# MotherForSmoothie_0.net
KiCad netlist of a schematic drawn in EAGLE
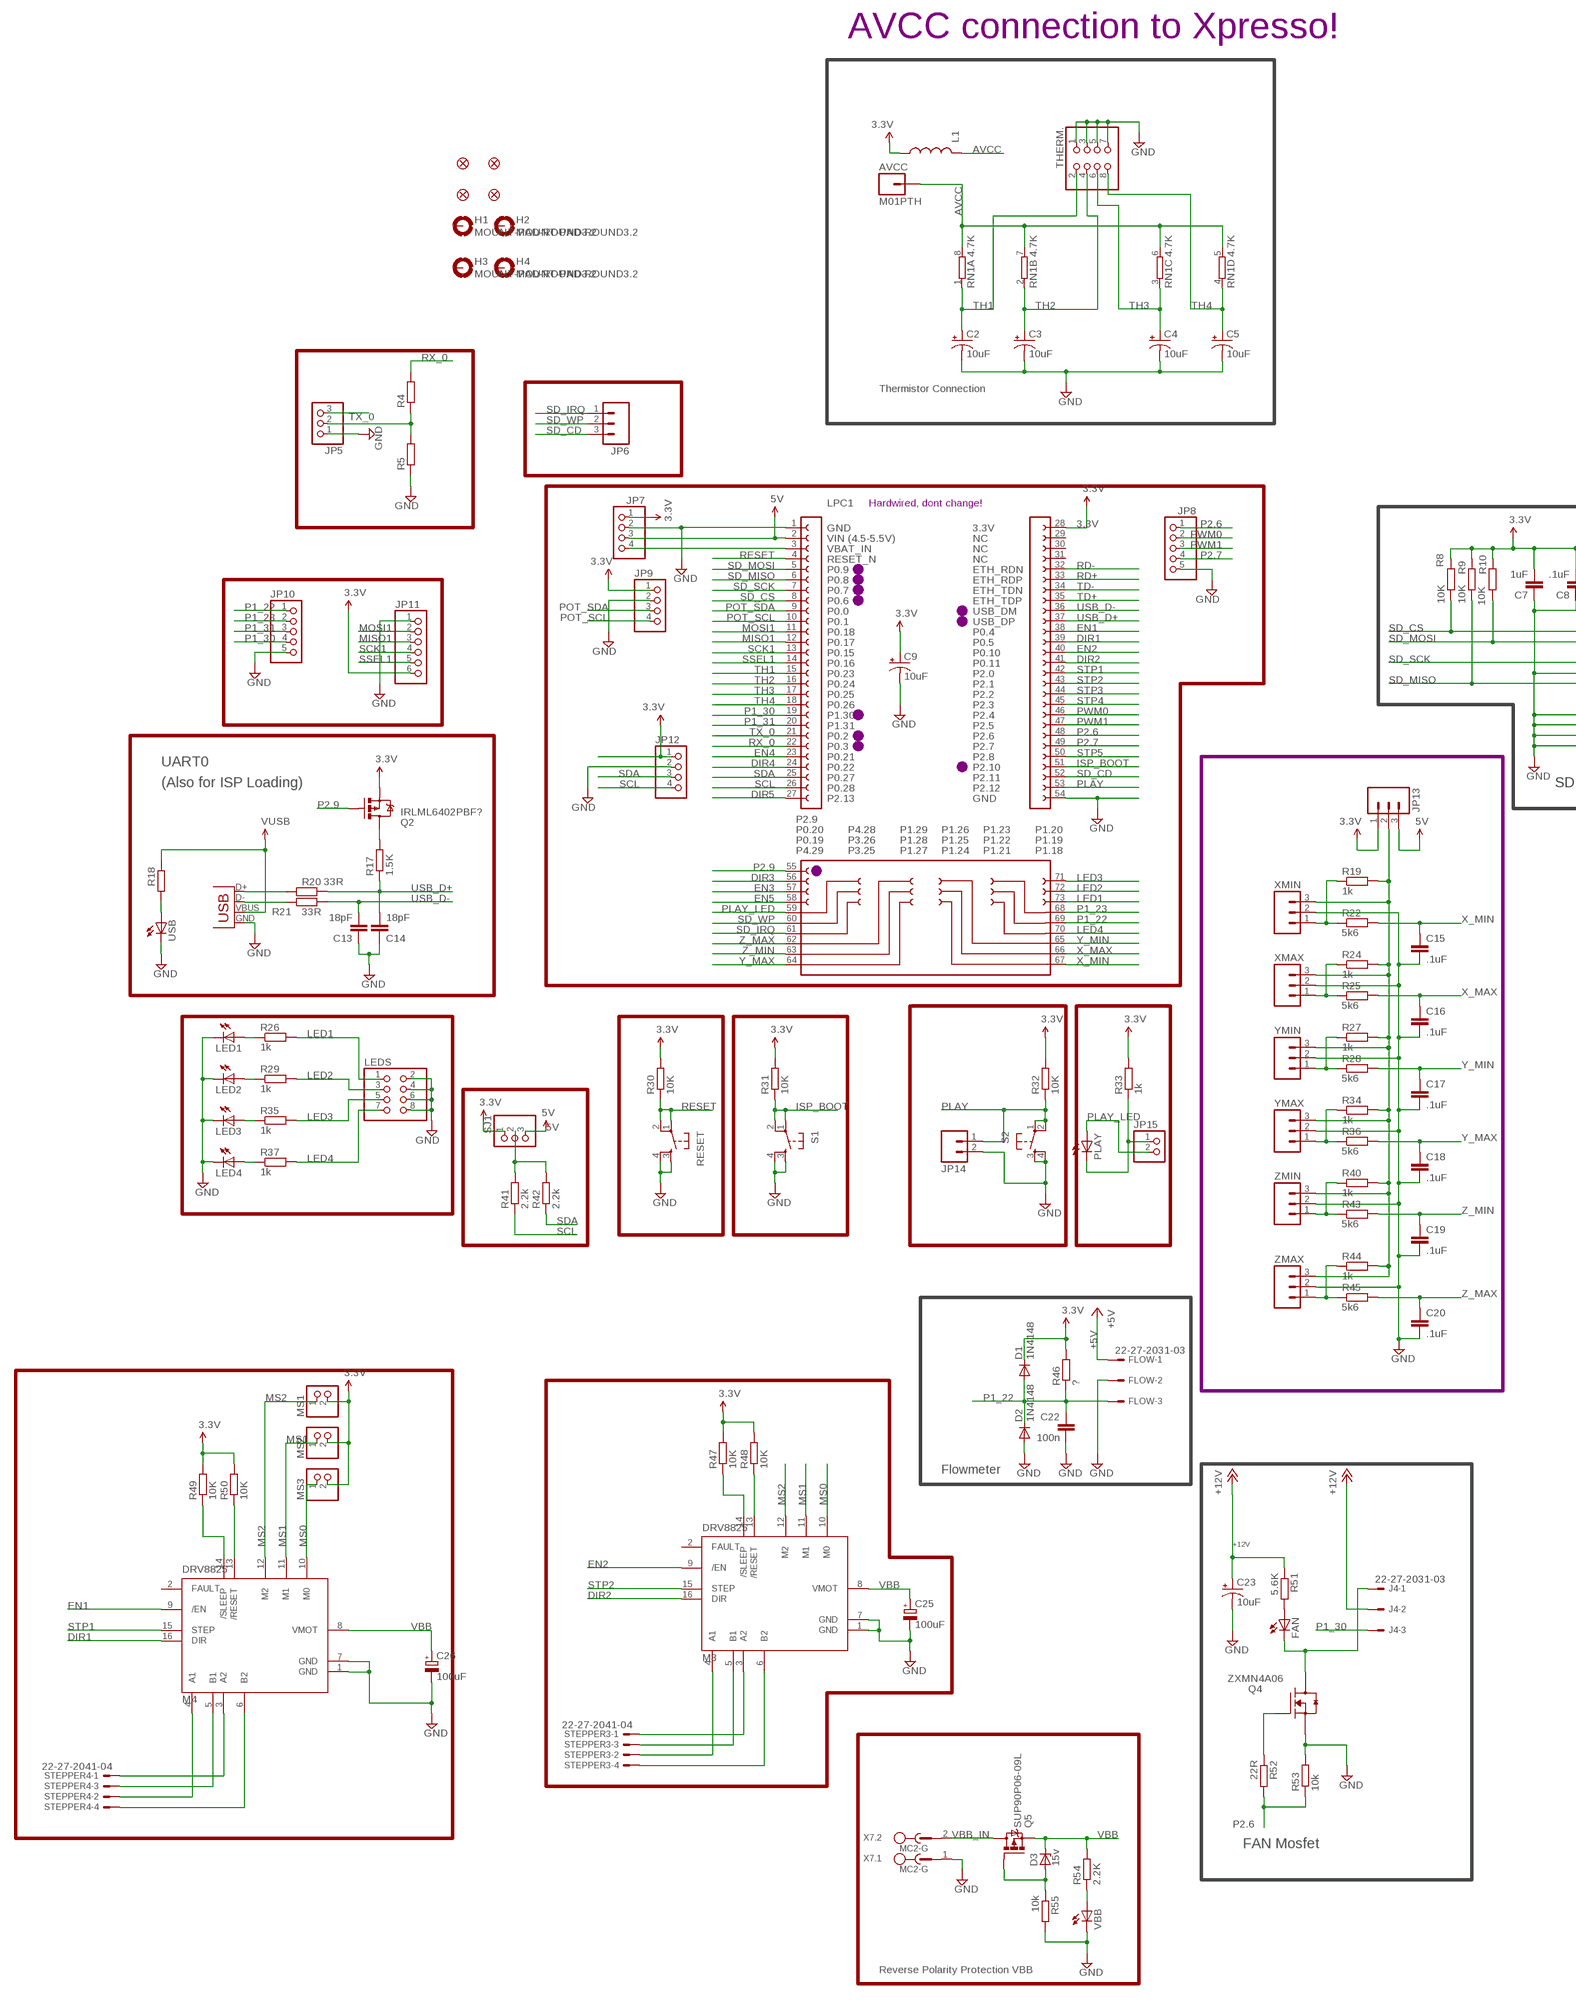
[diagram p0: schematic, sheet 1, part 1 of 2]
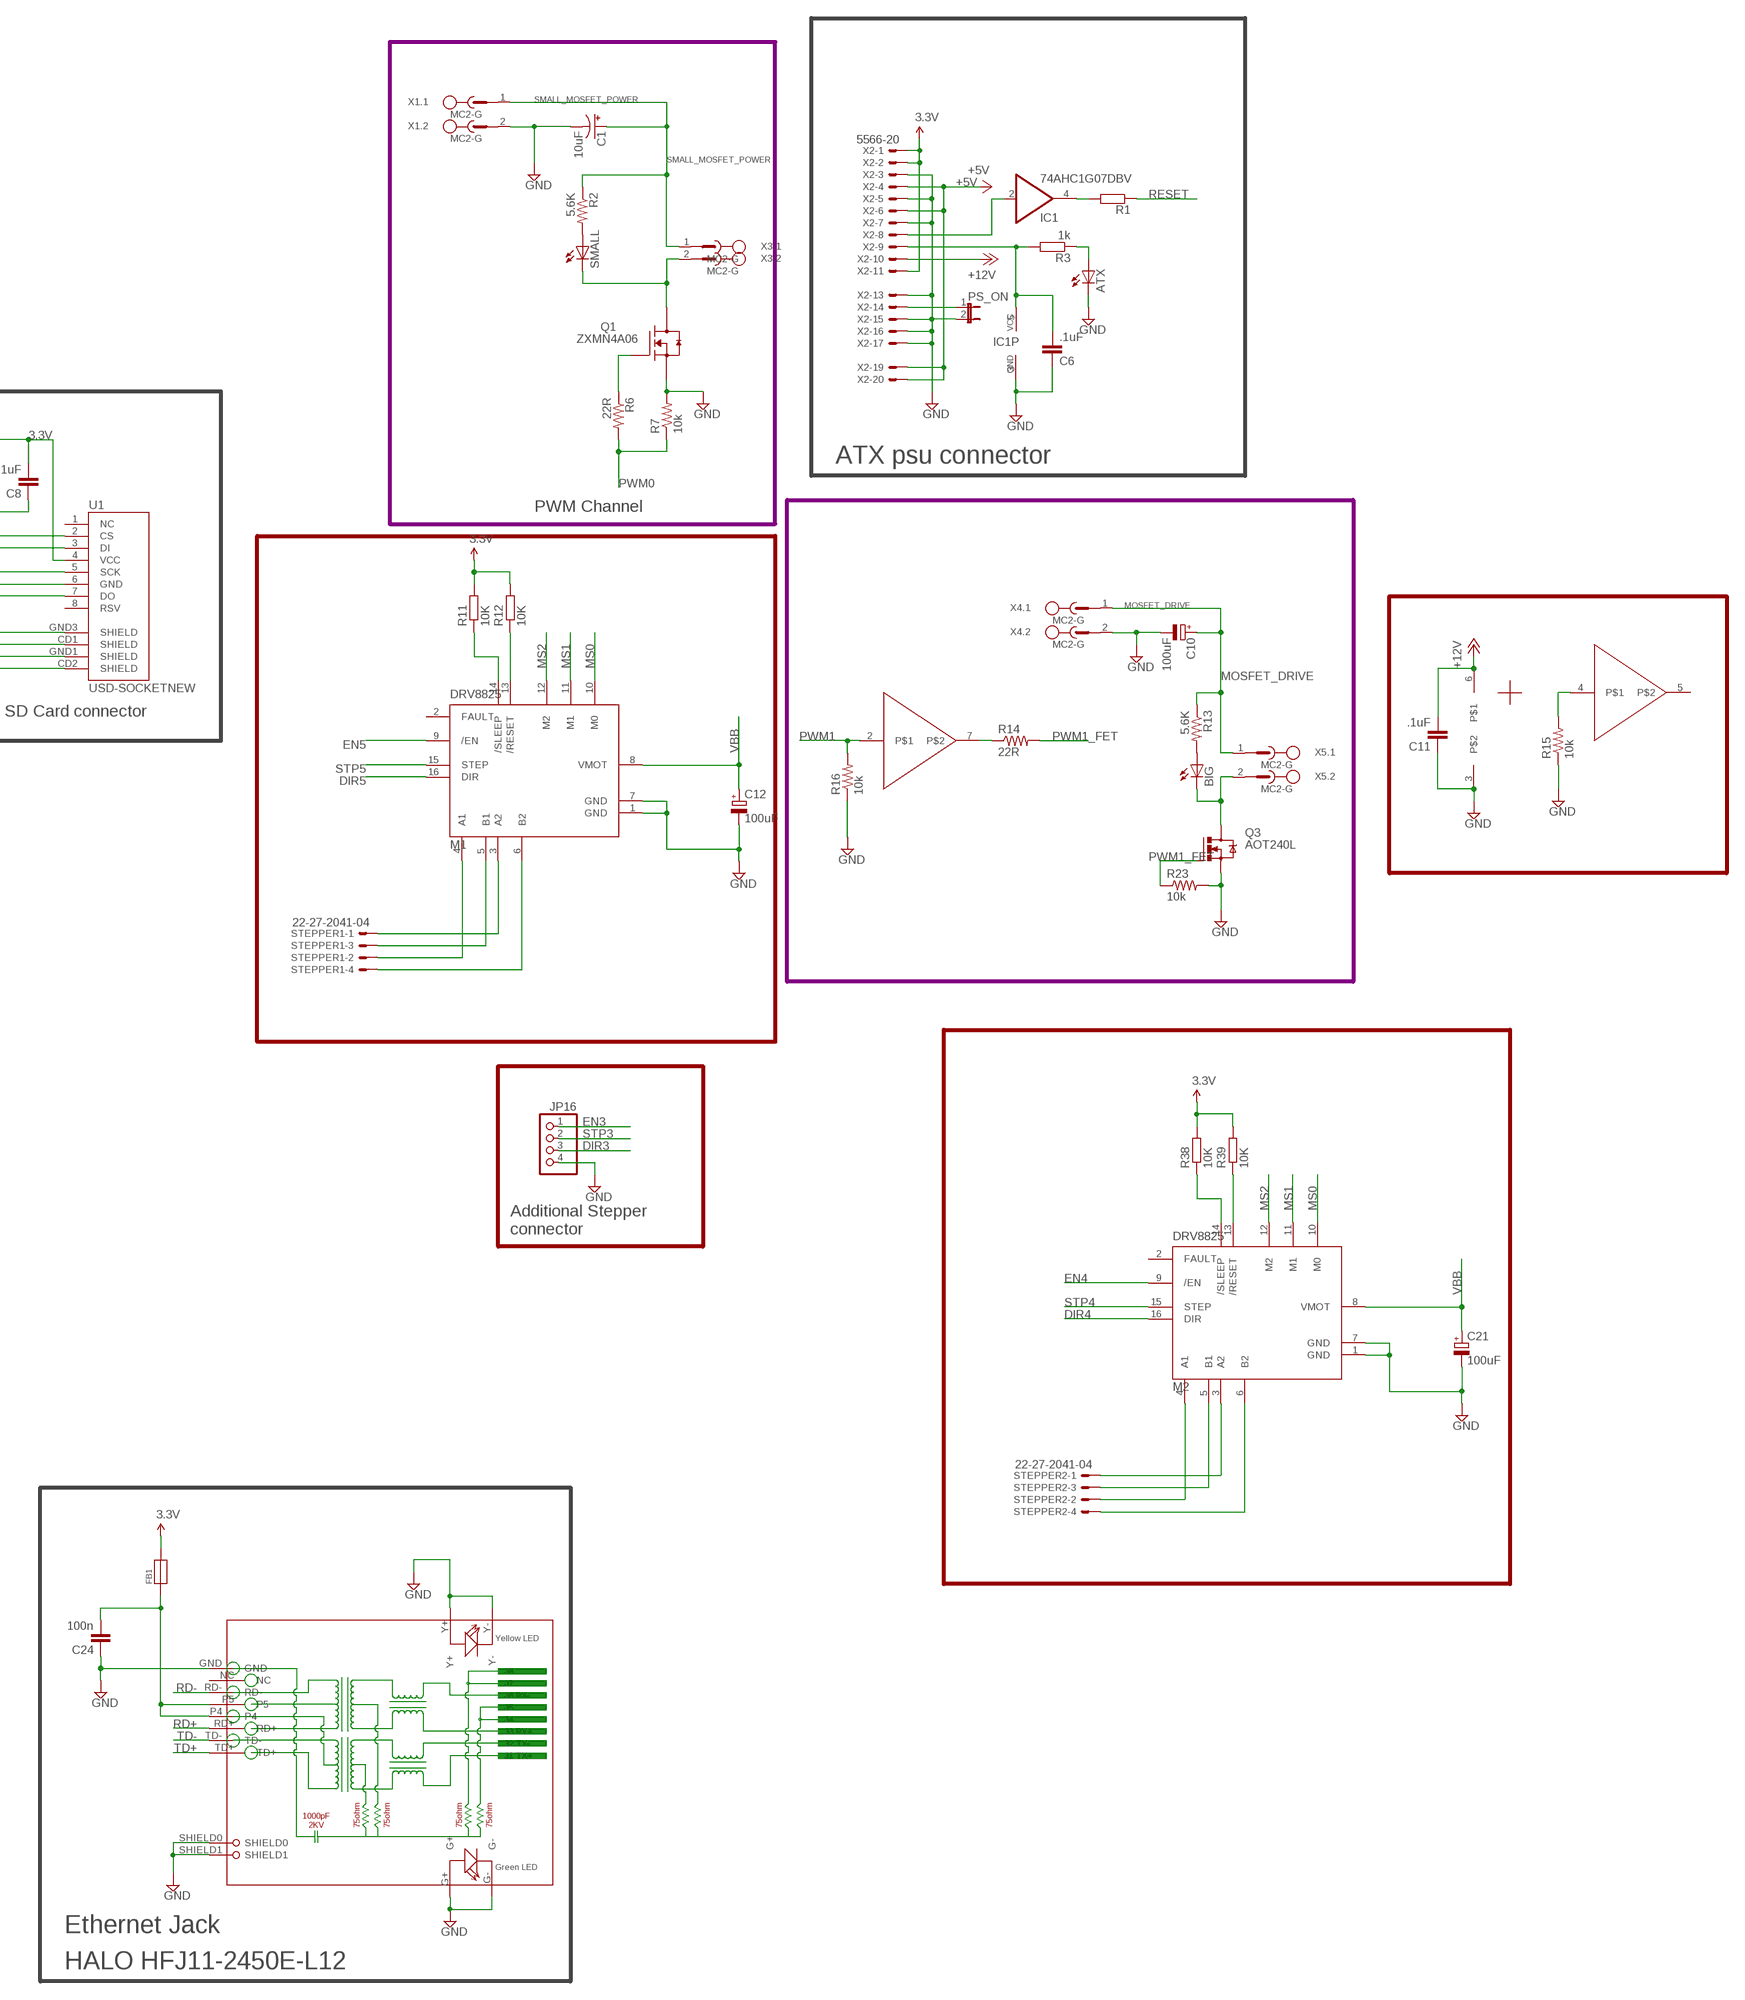
[diagram p1: schematic, sheet 1, part 2 of 2]

(export (version "E")
  (design (tool "Eeschema 10.0.6"))
  (components
    (comp (ref "ATX")
      (value "LEDCHIPLED_0805")
      (footprint "eagle-import:CHIPLED_0805")
      (libsource (lib "eagle-import") (part "LEDCHIPLED_0805"))
    )
    (comp (ref "AVCC")
      (value "M01PTH")
      (footprint "eagle-import:1X01")
      (libsource (lib "eagle-import") (part "M01PTH"))
    )
    (comp (ref "BIG")
      (value "LEDCHIP-LED0805")
      (footprint "eagle-import:CHIP-LED0805")
      (libsource (lib "eagle-import") (part "LEDCHIP-LED0805"))
    )
    (comp (ref "C1")
      (value "10uF")
      (footprint "eagle-import:EIA3216")
      (libsource (lib "eagle-import") (part "CAP_POL1206"))
    )
    (comp (ref "C2")
      (value "10uF")
      (footprint "eagle-import:EIA3216")
      (libsource (lib "eagle-import") (part "CAP_POL1206"))
    )
    (comp (ref "C3")
      (value "10uF")
      (footprint "eagle-import:EIA3216")
      (libsource (lib "eagle-import") (part "CAP_POL1206"))
    )
    (comp (ref "C4")
      (value "10uF")
      (footprint "eagle-import:EIA3216")
      (libsource (lib "eagle-import") (part "CAP_POL1206"))
    )
    (comp (ref "C5")
      (value "10uF")
      (footprint "eagle-import:EIA3216")
      (libsource (lib "eagle-import") (part "CAP_POL1206"))
    )
    (comp (ref "C6")
      (value ".1uF")
      (footprint "eagle-import:C0603")
      (libsource (lib "eagle-import") (part "C-EUC0603"))
    )
    (comp (ref "C7")
      (value "1uF")
      (footprint "eagle-import:C0603")
      (libsource (lib "eagle-import") (part "C-EUC0603"))
    )
    (comp (ref "C8")
      (value ".1uF")
      (footprint "eagle-import:C0603")
      (libsource (lib "eagle-import") (part "C-EUC0603"))
    )
    (comp (ref "C9")
      (value "10uF")
      (footprint "eagle-import:EIA6032")
      (libsource (lib "eagle-import") (part "CAP_POL6032"))
    )
    (comp (ref "C10")
      (value "100uF")
      (footprint "eagle-import:E5-8,5")
      (libsource (lib "eagle-import") (part "CPOL-EUE5-8.5"))
    )
    (comp (ref "C11")
      (value ".1uF")
      (footprint "eagle-import:C0603")
      (libsource (lib "eagle-import") (part "C-EUC0603"))
    )
    (comp (ref "C12")
      (value "100uF")
      (footprint "eagle-import:E5-8,5")
      (libsource (lib "eagle-import") (part "CPOL-EUE5-8.5"))
    )
    (comp (ref "C13")
      (value "18pF")
      (footprint "eagle-import:C0603")
      (libsource (lib "eagle-import") (part "C-EUC0603"))
    )
    (comp (ref "C14")
      (value "18pF")
      (footprint "eagle-import:C0603")
      (libsource (lib "eagle-import") (part "C-EUC0603"))
    )
    (comp (ref "C15")
      (value ".1uF")
      (footprint "eagle-import:C0603")
      (libsource (lib "eagle-import") (part "C-EUC0603"))
    )
    (comp (ref "C16")
      (value ".1uF")
      (footprint "eagle-import:C0603")
      (libsource (lib "eagle-import") (part "C-EUC0603"))
    )
    (comp (ref "C17")
      (value ".1uF")
      (footprint "eagle-import:C0603")
      (libsource (lib "eagle-import") (part "C-EUC0603"))
    )
    (comp (ref "C18")
      (value ".1uF")
      (footprint "eagle-import:C0603")
      (libsource (lib "eagle-import") (part "C-EUC0603"))
    )
    (comp (ref "C19")
      (value ".1uF")
      (footprint "eagle-import:C0603")
      (libsource (lib "eagle-import") (part "C-EUC0603"))
    )
    (comp (ref "C20")
      (value ".1uF")
      (footprint "eagle-import:C0603")
      (libsource (lib "eagle-import") (part "C-EUC0603"))
    )
    (comp (ref "C21")
      (value "100uF")
      (footprint "eagle-import:E5-8,5")
      (libsource (lib "eagle-import") (part "CPOL-EUE5-8.5"))
    )
    (comp (ref "C22")
      (value "100n")
      (footprint "eagle-import:C0603")
      (libsource (lib "eagle-import") (part "C-EUC0603"))
    )
    (comp (ref "C23")
      (value "10uF")
      (footprint "eagle-import:EIA3216")
      (libsource (lib "eagle-import") (part "CAP_POL1206"))
    )
    (comp (ref "C24")
      (value "100n")
      (footprint "eagle-import:C0603")
      (libsource (lib "eagle-import") (part "C-EUC0603"))
    )
    (comp (ref "C25")
      (value "100uF")
      (footprint "eagle-import:E5-8,5")
      (libsource (lib "eagle-import") (part "CPOL-EUE5-8.5"))
    )
    (comp (ref "C26")
      (value "100uF")
      (footprint "eagle-import:E5-8,5")
      (libsource (lib "eagle-import") (part "CPOL-EUE5-8.5"))
    )
    (comp (ref "D1")
      (value "1N4148")
      (footprint "eagle-import:MINIMELF")
      (libsource (lib "eagle-import") (part "DIODE-MINIMELF"))
    )
    (comp (ref "D2")
      (value "1N4148")
      (footprint "eagle-import:MINIMELF")
      (libsource (lib "eagle-import") (part "DIODE-MINIMELF"))
    )
    (comp (ref "D3")
      (value "15v")
      (footprint "eagle-import:SMB")
      (libsource (lib "eagle-import") (part "ZENER-DIODESMB"))
    )
    (comp (ref "FAN")
      (value "LEDCHIPLED_0805")
      (footprint "eagle-import:CHIPLED_0805")
      (libsource (lib "eagle-import") (part "LEDCHIPLED_0805"))
    )
    (comp (ref "FB1")
      (value "FERRITE")
      (footprint "eagle-import:0603")
      (libsource (lib "eagle-import") (part "FERRITE"))
    )
    (comp (ref "FLOW")
      (value "22-27-2031-03")
      (footprint "eagle-import:6410-03")
      (libsource (lib "eagle-import") (part "22-?-0327-2031"))
    )
    (comp (ref "H1")
      (value "MOUNT-PAD-ROUND3.2")
      (footprint "eagle-import:3,2-PAD")
      (libsource (lib "eagle-import") (part "MOUNT-PAD-ROUND3.2"))
    )
    (comp (ref "H2")
      (value "MOUNT-PAD-ROUND3.2")
      (footprint "eagle-import:3,2-PAD")
      (libsource (lib "eagle-import") (part "MOUNT-PAD-ROUND3.2"))
    )
    (comp (ref "H3")
      (value "MOUNT-PAD-ROUND3.2")
      (footprint "eagle-import:3,2-PAD")
      (libsource (lib "eagle-import") (part "MOUNT-PAD-ROUND3.2"))
    )
    (comp (ref "H4")
      (value "MOUNT-PAD-ROUND3.2")
      (footprint "eagle-import:3,2-PAD")
      (libsource (lib "eagle-import") (part "MOUNT-PAD-ROUND3.2"))
    )
    (comp (ref "IC1")
      (value "74AHC1G07DBV")
      (footprint "eagle-import:SOT23-5")
      (libsource (lib "eagle-import") (part "741G07DBVAHC"))
    )
    (comp (ref "IC2")
      (value "TC4427")
      (footprint "eagle-import:SOIC8")
      (libsource (lib "eagle-import") (part "TC4427"))
    )
    (comp (ref "J4")
      (value "22-27-2031-03")
      (footprint "eagle-import:6410-03")
      (libsource (lib "eagle-import") (part "22-?-0327-2031"))
    )
    (comp (ref "JP1")
      (value "FIDUCIAL1X2")
      (footprint "eagle-import:FIDUCIAL-1X2")
      (libsource (lib "eagle-import") (part "FIDUCIAL1X2"))
    )
    (comp (ref "JP2")
      (value "FIDUCIAL1X2")
      (footprint "eagle-import:FIDUCIAL-1X2")
      (libsource (lib "eagle-import") (part "FIDUCIAL1X2"))
    )
    (comp (ref "JP3")
      (value "FIDUCIAL1X2")
      (footprint "eagle-import:FIDUCIAL-1X2")
      (libsource (lib "eagle-import") (part "FIDUCIAL1X2"))
    )
    (comp (ref "JP4")
      (value "FIDUCIAL1X2")
      (footprint "eagle-import:FIDUCIAL-1X2")
      (libsource (lib "eagle-import") (part "FIDUCIAL1X2"))
    )
    (comp (ref "JP5")
      (value "PINHD-1X3_2.54-SMD")
      (footprint "eagle-import:1X03SMD")
      (libsource (lib "eagle-import") (part "PINHD-1X3_2.54-SMD"))
    )
    (comp (ref "JP6")
      (value "M031X03_NO_SILK")
      (footprint "eagle-import:1X03_NO_SILK")
      (libsource (lib "eagle-import") (part "M031X03_NO_SILK"))
    )
    (comp (ref "JP7")
      (value "PINHD-1X4_2.54-SMD")
      (footprint "eagle-import:1X04SMD")
      (libsource (lib "eagle-import") (part "PINHD-1X4_2.54-SMD"))
    )
    (comp (ref "JP8")
      (value "PINHD-1X5_2.54-SMD")
      (footprint "eagle-import:1X05SMD")
      (libsource (lib "eagle-import") (part "PINHD-1X5_2.54-SMD"))
    )
    (comp (ref "JP9")
      (value "PINHD-1X4_2.54-SMD")
      (footprint "eagle-import:1X04SMD")
      (libsource (lib "eagle-import") (part "PINHD-1X4_2.54-SMD"))
    )
    (comp (ref "JP10")
      (value "PINHD-1X5_2.54-SMD")
      (footprint "eagle-import:1X05SMD")
      (libsource (lib "eagle-import") (part "PINHD-1X5_2.54-SMD"))
    )
    (comp (ref "JP11")
      (value "PINHD-1X6_2.54-SMD")
      (footprint "eagle-import:1X06SMD")
      (libsource (lib "eagle-import") (part "PINHD-1X6_2.54-SMD"))
    )
    (comp (ref "JP12")
      (value "PINHD-1X4_2.54-SMD")
      (footprint "eagle-import:1X04SMD")
      (libsource (lib "eagle-import") (part "PINHD-1X4_2.54-SMD"))
    )
    (comp (ref "JP13")
      (value "M031X03_NO_SILK")
      (footprint "eagle-import:1X03_NO_SILK")
      (libsource (lib "eagle-import") (part "M031X03_NO_SILK"))
    )
    (comp (ref "JP14")
      (value "M02PTH")
      (footprint "eagle-import:1X02")
      (libsource (lib "eagle-import") (part "M02PTH"))
    )
    (comp (ref "JP15")
      (value "PINHD-1X2_2.54-SMD")
      (footprint "eagle-import:1X02SMD")
      (libsource (lib "eagle-import") (part "PINHD-1X2_2.54-SMD"))
    )
    (comp (ref "JP16")
      (value "PINHD-1X4_2.54-SMD")
      (footprint "eagle-import:1X04SMD")
      (libsource (lib "eagle-import") (part "PINHD-1X4_2.54-SMD"))
    )
    (comp (ref "L1")
      (value "INDUCTOR0603")
      (footprint "eagle-import:0603")
      (libsource (lib "eagle-import") (part "INDUCTOR0603"))
    )
    (comp (ref "LED1")
      (value "LEDCHIP-LED0805")
      (footprint "eagle-import:CHIP-LED0805")
      (libsource (lib "eagle-import") (part "LEDCHIP-LED0805"))
    )
    (comp (ref "LED2")
      (value "LEDCHIP-LED0805")
      (footprint "eagle-import:CHIP-LED0805")
      (libsource (lib "eagle-import") (part "LEDCHIP-LED0805"))
    )
    (comp (ref "LED3")
      (value "LEDCHIP-LED0805")
      (footprint "eagle-import:CHIP-LED0805")
      (libsource (lib "eagle-import") (part "LEDCHIP-LED0805"))
    )
    (comp (ref "LED4")
      (value "LEDCHIP-LED0805")
      (footprint "eagle-import:CHIP-LED0805")
      (libsource (lib "eagle-import") (part "LEDCHIP-LED0805"))
    )
    (comp (ref "LEDS")
      (value "PINHD-2X4_2.54-SMD")
      (footprint "eagle-import:2X04SMD")
      (libsource (lib "eagle-import") (part "PINHD-2X4_2.54-SMD"))
    )
    (comp (ref "LPC1")
      (value "LPCXPRESSO_LPC1769SMD_PART")
      (footprint "eagle-import:LPCXPRESSO_LPC1769_SMD")
      (libsource (lib "eagle-import") (part "LPCXPRESSO_LPC1769SMD_PART"))
    )
    (comp (ref "M1")
      (value "DRV8825")
      (footprint "eagle-import:DRV8825")
      (libsource (lib "eagle-import") (part "DRV8825"))
    )
    (comp (ref "M2")
      (value "DRV8825")
      (footprint "eagle-import:DRV8825")
      (libsource (lib "eagle-import") (part "DRV8825"))
    )
    (comp (ref "M3")
      (value "DRV8825")
      (footprint "eagle-import:DRV8825")
      (libsource (lib "eagle-import") (part "DRV8825"))
    )
    (comp (ref "M4")
      (value "DRV8825")
      (footprint "eagle-import:DRV8825")
      (libsource (lib "eagle-import") (part "DRV8825"))
    )
    (comp (ref "MS1")
      (value "PINHD-1X2_2.54-SMD")
      (footprint "eagle-import:1X02SMD")
      (libsource (lib "eagle-import") (part "PINHD-1X2_2.54-SMD"))
    )
    (comp (ref "MS2")
      (value "PINHD-1X2_2.54-SMD")
      (footprint "eagle-import:1X02SMD")
      (libsource (lib "eagle-import") (part "PINHD-1X2_2.54-SMD"))
    )
    (comp (ref "MS3")
      (value "PINHD-1X2_2.54-SMD")
      (footprint "eagle-import:1X02SMD")
      (libsource (lib "eagle-import") (part "PINHD-1X2_2.54-SMD"))
    )
    (comp (ref "PLAY")
      (value "LEDCHIPLED_0805")
      (footprint "eagle-import:CHIPLED_0805")
      (libsource (lib "eagle-import") (part "LEDCHIPLED_0805"))
    )
    (comp (ref "PS_ON")
      (value "JP1E")
      (footprint "eagle-import:JP1")
      (libsource (lib "eagle-import") (part "JP1E"))
    )
    (comp (ref "Q1")
      (value "ZXMN4A06")
      (footprint "eagle-import:SOT230P700X160-4N")
      (libsource (lib "eagle-import") (part "MOSFET-NCH_SOT-223"))
    )
    (comp (ref "Q2")
      (value "IRLML6402PBF?")
      (footprint "eagle-import:SOT23-3")
      (libsource (lib "eagle-import") (part "MOSFET-PCHANNELSMD"))
    )
    (comp (ref "Q3")
      (value "AOT240L")
      (footprint "eagle-import:TO220BV")
      (libsource (lib "eagle-import") (part "IRF540"))
    )
    (comp (ref "Q4")
      (value "ZXMN4A06")
      (footprint "eagle-import:SOT230P700X160-4N")
      (libsource (lib "eagle-import") (part "MOSFET-NCH_SOT-223"))
    )
    (comp (ref "Q5")
      (value "SUP90P06-09L")
      (footprint "eagle-import:TO220BV")
      (libsource (lib "eagle-import") (part "IRF9530"))
    )
    (comp (ref "R1")
      (value "R-EU_R0603")
      (footprint "eagle-import:R0603")
      (libsource (lib "eagle-import") (part "R-EU_R0603"))
    )
    (comp (ref "R2")
      (value "5.6K")
      (footprint "eagle-import:R0603")
      (libsource (lib "eagle-import") (part "R-US_R0603"))
    )
    (comp (ref "R3")
      (value "1k")
      (footprint "eagle-import:R0603")
      (libsource (lib "eagle-import") (part "R-EU_R0603"))
    )
    (comp (ref "R4")
      (value "R-EU_R0603")
      (footprint "eagle-import:R0603")
      (libsource (lib "eagle-import") (part "R-EU_R0603"))
    )
    (comp (ref "R5")
      (value "R-EU_R0603")
      (footprint "eagle-import:R0603")
      (libsource (lib "eagle-import") (part "R-EU_R0603"))
    )
    (comp (ref "R6")
      (value "22R")
      (footprint "eagle-import:R0603")
      (libsource (lib "eagle-import") (part "R-US_R0603"))
    )
    (comp (ref "R7")
      (value "10k")
      (footprint "eagle-import:R0603")
      (libsource (lib "eagle-import") (part "R-US_R0603"))
    )
    (comp (ref "R8")
      (value "10K")
      (footprint "eagle-import:R0603")
      (libsource (lib "eagle-import") (part "R-EU_R0603"))
    )
    (comp (ref "R9")
      (value "10K")
      (footprint "eagle-import:R0603")
      (libsource (lib "eagle-import") (part "R-EU_R0603"))
    )
    (comp (ref "R10")
      (value "10K")
      (footprint "eagle-import:R0603")
      (libsource (lib "eagle-import") (part "R-EU_R0603"))
    )
    (comp (ref "R11")
      (value "10K")
      (footprint "eagle-import:R0603")
      (libsource (lib "eagle-import") (part "R-EU_R0603"))
    )
    (comp (ref "R12")
      (value "10K")
      (footprint "eagle-import:R0603")
      (libsource (lib "eagle-import") (part "R-EU_R0603"))
    )
    (comp (ref "R13")
      (value "5.6K")
      (footprint "eagle-import:R0603")
      (libsource (lib "eagle-import") (part "R-US_R0603"))
    )
    (comp (ref "R14")
      (value "22R")
      (footprint "eagle-import:R0603")
      (libsource (lib "eagle-import") (part "R-US_R0603"))
    )
    (comp (ref "R15")
      (value "10k")
      (footprint "eagle-import:R0603")
      (libsource (lib "eagle-import") (part "R-US_R0603"))
    )
    (comp (ref "R16")
      (value "10k")
      (footprint "eagle-import:R0603")
      (libsource (lib "eagle-import") (part "R-US_R0603"))
    )
    (comp (ref "R17")
      (value "1.5K")
      (footprint "eagle-import:R0603")
      (libsource (lib "eagle-import") (part "R-EU_R0603"))
    )
    (comp (ref "R18")
      (value "R-EU_R0603")
      (footprint "eagle-import:R0603")
      (libsource (lib "eagle-import") (part "R-EU_R0603"))
    )
    (comp (ref "R19")
      (value "1k")
      (footprint "eagle-import:R0603")
      (libsource (lib "eagle-import") (part "R-EU_R0603"))
    )
    (comp (ref "R20")
      (value "33R")
      (footprint "eagle-import:R0603")
      (libsource (lib "eagle-import") (part "R-EU_R0603"))
    )
    (comp (ref "R21")
      (value "33R")
      (footprint "eagle-import:R0603")
      (libsource (lib "eagle-import") (part "R-EU_R0603"))
    )
    (comp (ref "R22")
      (value "5k6")
      (footprint "eagle-import:R0603")
      (libsource (lib "eagle-import") (part "R-EU_R0603"))
    )
    (comp (ref "R23")
      (value "10k")
      (footprint "eagle-import:R0603")
      (libsource (lib "eagle-import") (part "R-US_R0603"))
    )
    (comp (ref "R24")
      (value "1k")
      (footprint "eagle-import:R0603")
      (libsource (lib "eagle-import") (part "R-EU_R0603"))
    )
    (comp (ref "R25")
      (value "5k6")
      (footprint "eagle-import:R0603")
      (libsource (lib "eagle-import") (part "R-EU_R0603"))
    )
    (comp (ref "R26")
      (value "1k")
      (footprint "eagle-import:R0603")
      (libsource (lib "eagle-import") (part "R-EU_R0603"))
    )
    (comp (ref "R27")
      (value "1k")
      (footprint "eagle-import:R0603")
      (libsource (lib "eagle-import") (part "R-EU_R0603"))
    )
    (comp (ref "R28")
      (value "5k6")
      (footprint "eagle-import:R0603")
      (libsource (lib "eagle-import") (part "R-EU_R0603"))
    )
    (comp (ref "R29")
      (value "1k")
      (footprint "eagle-import:R0603")
      (libsource (lib "eagle-import") (part "R-EU_R0603"))
    )
    (comp (ref "R30")
      (value "10K")
      (footprint "eagle-import:R0603")
      (libsource (lib "eagle-import") (part "R-EU_R0603"))
    )
    (comp (ref "R31")
      (value "10K")
      (footprint "eagle-import:R0603")
      (libsource (lib "eagle-import") (part "R-EU_R0603"))
    )
    (comp (ref "R32")
      (value "10K")
      (footprint "eagle-import:R0603")
      (libsource (lib "eagle-import") (part "R-EU_R0603"))
    )
    (comp (ref "R33")
      (value "1k")
      (footprint "eagle-import:R0603")
      (libsource (lib "eagle-import") (part "R-EU_R0603"))
    )
    (comp (ref "R34")
      (value "1k")
      (footprint "eagle-import:R0603")
      (libsource (lib "eagle-import") (part "R-EU_R0603"))
    )
    (comp (ref "R35")
      (value "1k")
      (footprint "eagle-import:R0603")
      (libsource (lib "eagle-import") (part "R-EU_R0603"))
    )
    (comp (ref "R36")
      (value "5k6")
      (footprint "eagle-import:R0603")
      (libsource (lib "eagle-import") (part "R-EU_R0603"))
    )
    (comp (ref "R37")
      (value "1k")
      (footprint "eagle-import:R0603")
      (libsource (lib "eagle-import") (part "R-EU_R0603"))
    )
    (comp (ref "R38")
      (value "10K")
      (footprint "eagle-import:R0603")
      (libsource (lib "eagle-import") (part "R-EU_R0603"))
    )
    (comp (ref "R39")
      (value "10K")
      (footprint "eagle-import:R0603")
      (libsource (lib "eagle-import") (part "R-EU_R0603"))
    )
    (comp (ref "R40")
      (value "1k")
      (footprint "eagle-import:R0603")
      (libsource (lib "eagle-import") (part "R-EU_R0603"))
    )
    (comp (ref "R41")
      (value "2.2k")
      (footprint "eagle-import:R0603")
      (libsource (lib "eagle-import") (part "R-EU_R0603"))
    )
    (comp (ref "R42")
      (value "2.2k")
      (footprint "eagle-import:R0603")
      (libsource (lib "eagle-import") (part "R-EU_R0603"))
    )
    (comp (ref "R43")
      (value "5k6")
      (footprint "eagle-import:R0603")
      (libsource (lib "eagle-import") (part "R-EU_R0603"))
    )
    (comp (ref "R44")
      (value "1k")
      (footprint "eagle-import:R0603")
      (libsource (lib "eagle-import") (part "R-EU_R0603"))
    )
    (comp (ref "R45")
      (value "5k6")
      (footprint "eagle-import:R0603")
      (libsource (lib "eagle-import") (part "R-EU_R0603"))
    )
    (comp (ref "R46")
      (value "?")
      (footprint "eagle-import:R0603")
      (libsource (lib "eagle-import") (part "R-EU_R0603"))
    )
    (comp (ref "R47")
      (value "10K")
      (footprint "eagle-import:R0603")
      (libsource (lib "eagle-import") (part "R-EU_R0603"))
    )
    (comp (ref "R48")
      (value "10K")
      (footprint "eagle-import:R0603")
      (libsource (lib "eagle-import") (part "R-EU_R0603"))
    )
    (comp (ref "R49")
      (value "10K")
      (footprint "eagle-import:R0603")
      (libsource (lib "eagle-import") (part "R-EU_R0603"))
    )
    (comp (ref "R50")
      (value "10K")
      (footprint "eagle-import:R0603")
      (libsource (lib "eagle-import") (part "R-EU_R0603"))
    )
    (comp (ref "R51")
      (value "5.6K")
      (footprint "eagle-import:R0603")
      (libsource (lib "eagle-import") (part "R-EU_R0603"))
    )
    (comp (ref "R52")
      (value "22R")
      (footprint "eagle-import:R0603")
      (libsource (lib "eagle-import") (part "R-EU_R0603"))
    )
    (comp (ref "R53")
      (value "10k")
      (footprint "eagle-import:R0603")
      (libsource (lib "eagle-import") (part "R-EU_R0603"))
    )
    (comp (ref "R54")
      (value "2.2K")
      (footprint "eagle-import:R0603")
      (libsource (lib "eagle-import") (part "R-EU_R0603"))
    )
    (comp (ref "R55")
      (value "10k")
      (footprint "eagle-import:R0603")
      (libsource (lib "eagle-import") (part "R-EU_R0603"))
    )
    (comp (ref "RESET")
      (value "TAC_SWITCHSMD")
      (footprint "eagle-import:TACTILE_SWITCH_SMD")
      (libsource (lib "eagle-import") (part "TAC_SWITCHSMD"))
    )
    (comp (ref "RJ1")
      (value "HR911105A")
      (footprint "eagle-import:HR911105A")
      (libsource (lib "eagle-import") (part "HR911105A"))
    )
    (comp (ref "RN1")
      (value "4.7K")
      (footprint "eagle-import:0603-ARV")
      (libsource (lib "eagle-import") (part "4R-N0603-ARV"))
    )
    (comp (ref "S1")
      (value "TAC_SWITCHSMD")
      (footprint "eagle-import:TACTILE_SWITCH_SMD")
      (libsource (lib "eagle-import") (part "TAC_SWITCHSMD"))
    )
    (comp (ref "S2")
      (value "TAC_SWITCHSMD")
      (footprint "eagle-import:TACTILE_SWITCH_SMD")
      (libsource (lib "eagle-import") (part "TAC_SWITCHSMD"))
    )
    (comp (ref "SJ1")
      (value "PINHD-1X3_2.54-SMD")
      (footprint "eagle-import:1X03SMD")
      (libsource (lib "eagle-import") (part "PINHD-1X3_2.54-SMD"))
    )
    (comp (ref "SMALL")
      (value "LEDCHIP-LED0805")
      (footprint "eagle-import:CHIP-LED0805")
      (libsource (lib "eagle-import") (part "LEDCHIP-LED0805"))
    )
    (comp (ref "STEPPER1")
      (value "22-27-2041-04")
      (footprint "eagle-import:6410-04")
      (libsource (lib "eagle-import") (part "22-?-0427-2041"))
    )
    (comp (ref "STEPPER2")
      (value "22-27-2041-04")
      (footprint "eagle-import:6410-04")
      (libsource (lib "eagle-import") (part "22-?-0427-2041"))
    )
    (comp (ref "STEPPER3")
      (value "22-27-2041-04")
      (footprint "eagle-import:6410-04")
      (libsource (lib "eagle-import") (part "22-?-0427-2041"))
    )
    (comp (ref "STEPPER4")
      (value "22-27-2041-04")
      (footprint "eagle-import:6410-04")
      (libsource (lib "eagle-import") (part "22-?-0427-2041"))
    )
    (comp (ref "THERM.")
      (value "PINHD-2X4MICROMATCH-SMD")
      (footprint "eagle-import:SMDTOP8")
      (libsource (lib "eagle-import") (part "PINHD-2X4MICROMATCH-SMD"))
    )
    (comp (ref "U1")
      (value "USD-SOCKETNEW")
      (footprint "eagle-import:MICRO-SD-SOCKET-PP")
      (libsource (lib "eagle-import") (part "USD-SOCKETNEW"))
    )
    (comp (ref "USB")
      (value "LEDCHIPLED_0805")
      (footprint "eagle-import:CHIPLED_0805")
      (libsource (lib "eagle-import") (part "LEDCHIPLED_0805"))
    )
    (comp (ref "VBB")
      (value "LEDCHIPLED_0805")
      (footprint "eagle-import:CHIPLED_0805")
      (libsource (lib "eagle-import") (part "LEDCHIPLED_0805"))
    )
    (comp (ref "X1")
      (value "MC2-G")
      (footprint "eagle-import:MC2-G")
      (libsource (lib "eagle-import") (part "MC2-G"))
    )
    (comp (ref "X2")
      (value "5566-20")
      (footprint "eagle-import:5566-20")
      (libsource (lib "eagle-import") (part "5566-20"))
    )
    (comp (ref "X3")
      (value "MC2-G")
      (footprint "eagle-import:MC2-G")
      (libsource (lib "eagle-import") (part "MC2-G"))
    )
    (comp (ref "X4")
      (value "MC2-G")
      (footprint "eagle-import:MC2-G")
      (libsource (lib "eagle-import") (part "MC2-G"))
    )
    (comp (ref "X5")
      (value "MC2-G")
      (footprint "eagle-import:MC2-G")
      (libsource (lib "eagle-import") (part "MC2-G"))
    )
    (comp (ref "X6")
      (value "USB-MICROB")
      (footprint "eagle-import:USB-MICROB")
      (libsource (lib "eagle-import") (part "USB-MICROB"))
    )
    (comp (ref "X7")
      (value "MC2-G")
      (footprint "eagle-import:MC2-G")
      (libsource (lib "eagle-import") (part "MC2-G"))
    )
    (comp (ref "XMAX")
      (value "M031X03_NO_SILK")
      (footprint "eagle-import:1X03_NO_SILK")
      (libsource (lib "eagle-import") (part "M031X03_NO_SILK"))
    )
    (comp (ref "XMIN")
      (value "M031X03_NO_SILK")
      (footprint "eagle-import:1X03_NO_SILK")
      (libsource (lib "eagle-import") (part "M031X03_NO_SILK"))
    )
    (comp (ref "YMAX")
      (value "M031X03_NO_SILK")
      (footprint "eagle-import:1X03_NO_SILK")
      (libsource (lib "eagle-import") (part "M031X03_NO_SILK"))
    )
    (comp (ref "YMIN")
      (value "M031X03_NO_SILK")
      (footprint "eagle-import:1X03_NO_SILK")
      (libsource (lib "eagle-import") (part "M031X03_NO_SILK"))
    )
    (comp (ref "ZMAX")
      (value "M031X03_NO_SILK")
      (footprint "eagle-import:1X03_NO_SILK")
      (libsource (lib "eagle-import") (part "M031X03_NO_SILK"))
    )
    (comp (ref "ZMIN")
      (value "M031X03_NO_SILK")
      (footprint "eagle-import:1X03_NO_SILK")
      (libsource (lib "eagle-import") (part "M031X03_NO_SILK"))
    )
  )
  (nets
    (net (code "1") (name "+5V") (class "Default")
      (node (ref "FLOW") (pin "1") (pinfunction "S_1") (pintype "passive"))
      (node (ref "X2") (pin "19") (pinfunction "S_19") (pintype "passive"))
      (node (ref "X2") (pin "20") (pinfunction "S_20") (pintype "passive"))
      (node (ref "X2") (pin "4") (pinfunction "S_4") (pintype "passive"))
      (node (ref "X2") (pin "6") (pinfunction "S_6") (pintype "passive"))
    )
    (net (code "2") (name "+12V") (class "Default")
      (node (ref "C11") (pin "2") (pinfunction "2_2") (pintype "passive"))
      (node (ref "C23") (pin "A") (pinfunction "+_A") (pintype "passive"))
      (node (ref "IC2") (pin "6") (pinfunction "P$1_6") (pintype "bidirectional"))
      (node (ref "J4") (pin "2") (pinfunction "S_2") (pintype "passive"))
      (node (ref "R51") (pin "1") (pinfunction "1_1") (pintype "passive"))
      (node (ref "X2") (pin "10") (pinfunction "S_10") (pintype "passive"))
    )
    (net (code "3") (name "/AVCC") (class "Default")
      (node (ref "AVCC") (pin "1") (pinfunction "1_1") (pintype "passive"))
      (node (ref "L1") (pin "1") (pinfunction "1_1") (pintype "passive"))
      (node (ref "RN1") (pin "5") (pinfunction "2_5") (pintype "passive"))
      (node (ref "RN1") (pin "6") (pinfunction "2_6") (pintype "passive"))
      (node (ref "RN1") (pin "7") (pinfunction "2_7") (pintype "passive"))
      (node (ref "RN1") (pin "8") (pinfunction "2_8") (pintype "passive"))
    )
    (net (code "4") (name "/DIR1") (class "Default")
      (node (ref "LPC1") (pin "39") (pinfunction "39_39") (pintype "passive"))
      (node (ref "M4") (pin "16") (pinfunction "DIR_16") (pintype "input"))
    )
    (net (code "5") (name "/DIR2") (class "Default")
      (node (ref "LPC1") (pin "41") (pinfunction "41_41") (pintype "passive"))
      (node (ref "M3") (pin "16") (pinfunction "DIR_16") (pintype "input"))
    )
    (net (code "6") (name "/DIR3") (class "Default")
      (node (ref "JP16") (pin "3") (pinfunction "3_3") (pintype "passive"))
      (node (ref "LPC1") (pin "56") (pinfunction "56_56") (pintype "passive"))
    )
    (net (code "7") (name "/DIR4") (class "Default")
      (node (ref "LPC1") (pin "24") (pinfunction "24_24") (pintype "passive"))
      (node (ref "M2") (pin "16") (pinfunction "DIR_16") (pintype "input"))
    )
    (net (code "8") (name "/DIR5") (class "Default")
      (node (ref "LPC1") (pin "27") (pinfunction "27_27") (pintype "passive"))
      (node (ref "M1") (pin "16") (pinfunction "DIR_16") (pintype "input"))
    )
    (net (code "9") (name "/EN1") (class "Default")
      (node (ref "LPC1") (pin "38") (pinfunction "38_38") (pintype "passive"))
      (node (ref "M4") (pin "9") (pinfunction "/EN_9") (pintype "input"))
    )
    (net (code "10") (name "/EN2") (class "Default")
      (node (ref "LPC1") (pin "40") (pinfunction "40_40") (pintype "passive"))
      (node (ref "M3") (pin "9") (pinfunction "/EN_9") (pintype "input"))
    )
    (net (code "11") (name "/EN3") (class "Default")
      (node (ref "JP16") (pin "1") (pinfunction "1_1") (pintype "passive"))
      (node (ref "LPC1") (pin "57") (pinfunction "57_57") (pintype "passive"))
    )
    (net (code "12") (name "/EN4") (class "Default")
      (node (ref "LPC1") (pin "23") (pinfunction "23_23") (pintype "passive"))
      (node (ref "M2") (pin "9") (pinfunction "/EN_9") (pintype "input"))
    )
    (net (code "13") (name "/EN5") (class "Default")
      (node (ref "LPC1") (pin "58") (pinfunction "58_58") (pintype "passive"))
      (node (ref "M1") (pin "9") (pinfunction "/EN_9") (pintype "input"))
    )
    (net (code "14") (name "/ISP_BOOT") (class "Default")
      (node (ref "LPC1") (pin "51") (pinfunction "51_51") (pintype "passive"))
      (node (ref "R31") (pin "1") (pinfunction "1_1") (pintype "passive"))
      (node (ref "S1") (pin "1") (pinfunction "1_1") (pintype "passive"))
      (node (ref "S1") (pin "2") (pinfunction "2_2") (pintype "passive"))
    )
    (net (code "15") (name "/LED1") (class "Default")
      (node (ref "LEDS") (pin "1") (pinfunction "1_1") (pintype "passive"))
      (node (ref "LPC1") (pin "73") (pinfunction "73_73") (pintype "passive"))
      (node (ref "R26") (pin "2") (pinfunction "2_2") (pintype "passive"))
    )
    (net (code "16") (name "/LED2") (class "Default")
      (node (ref "LEDS") (pin "3") (pinfunction "3_3") (pintype "passive"))
      (node (ref "LPC1") (pin "72") (pinfunction "72_72") (pintype "passive"))
      (node (ref "R29") (pin "2") (pinfunction "2_2") (pintype "passive"))
    )
    (net (code "17") (name "/LED3") (class "Default")
      (node (ref "LEDS") (pin "5") (pinfunction "5_5") (pintype "passive"))
      (node (ref "LPC1") (pin "71") (pinfunction "71_71") (pintype "passive"))
      (node (ref "R35") (pin "2") (pinfunction "2_2") (pintype "passive"))
    )
    (net (code "18") (name "/LED4") (class "Default")
      (node (ref "LEDS") (pin "7") (pinfunction "7_7") (pintype "passive"))
      (node (ref "LPC1") (pin "70") (pinfunction "70_70") (pintype "passive"))
      (node (ref "R37") (pin "2") (pinfunction "2_2") (pintype "passive"))
    )
    (net (code "19") (name "/MISO1") (class "Default")
      (node (ref "JP11") (pin "3") (pinfunction "3_3") (pintype "passive"))
      (node (ref "LPC1") (pin "12") (pinfunction "12_12") (pintype "passive"))
    )
    (net (code "20") (name "/MOSFET_DRIVE") (class "Default")
      (node (ref "C10") (pin "+") (pinfunction "+_+") (pintype "passive"))
      (node (ref "R13") (pin "1") (pinfunction "1_1") (pintype "passive"))
      (node (ref "X4") (pin "1") (pinfunction "SK_1") (pintype "passive"))
      (node (ref "X5") (pin "1") (pinfunction "SK_1") (pintype "passive"))
    )
    (net (code "21") (name "/MOSI1") (class "Default")
      (node (ref "JP11") (pin "2") (pinfunction "2_2") (pintype "passive"))
      (node (ref "LPC1") (pin "11") (pinfunction "11_11") (pintype "passive"))
    )
    (net (code "22") (name "/MS0") (class "Default")
      (node (ref "M1") (pin "10") (pinfunction "M0_10") (pintype "input"))
      (node (ref "M2") (pin "10") (pinfunction "M0_10") (pintype "input"))
      (node (ref "M3") (pin "10") (pinfunction "M0_10") (pintype "input"))
      (node (ref "M4") (pin "10") (pinfunction "M0_10") (pintype "input"))
      (node (ref "MS3") (pin "1") (pinfunction "1_1") (pintype "passive"))
    )
    (net (code "23") (name "/MS1") (class "Default")
      (node (ref "M1") (pin "11") (pinfunction "M1_11") (pintype "input"))
      (node (ref "M2") (pin "11") (pinfunction "M1_11") (pintype "input"))
      (node (ref "M3") (pin "11") (pinfunction "M1_11") (pintype "input"))
      (node (ref "M4") (pin "11") (pinfunction "M1_11") (pintype "input"))
      (node (ref "MS2") (pin "1") (pinfunction "1_1") (pintype "passive"))
    )
    (net (code "24") (name "/MS2") (class "Default")
      (node (ref "M1") (pin "12") (pinfunction "M2_12") (pintype "input"))
      (node (ref "M2") (pin "12") (pinfunction "M2_12") (pintype "input"))
      (node (ref "M3") (pin "12") (pinfunction "M2_12") (pintype "input"))
      (node (ref "M4") (pin "12") (pinfunction "M2_12") (pintype "input"))
      (node (ref "MS1") (pin "1") (pinfunction "1_1") (pintype "passive"))
    )
    (net (code "25") (name "/P1_22") (class "Default")
      (node (ref "C22") (pin "1") (pinfunction "1_1") (pintype "passive"))
      (node (ref "D1") (pin "A") (pinfunction "A_A") (pintype "passive"))
      (node (ref "D2") (pin "C") (pinfunction "C_C") (pintype "passive"))
      (node (ref "FLOW") (pin "3") (pinfunction "S_3") (pintype "passive"))
      (node (ref "JP10") (pin "1") (pinfunction "1_1") (pintype "passive"))
      (node (ref "LPC1") (pin "69") (pinfunction "69_69") (pintype "passive"))
      (node (ref "R46") (pin "1") (pinfunction "1_1") (pintype "passive"))
    )
    (net (code "26") (name "/P1_23") (class "Default")
      (node (ref "JP10") (pin "2") (pinfunction "2_2") (pintype "passive"))
      (node (ref "LPC1") (pin "68") (pinfunction "68_68") (pintype "passive"))
    )
    (net (code "27") (name "/P1_30") (class "Default")
      (node (ref "J4") (pin "3") (pinfunction "S_3") (pintype "passive"))
      (node (ref "JP10") (pin "4") (pinfunction "4_4") (pintype "passive"))
      (node (ref "LPC1") (pin "19") (pinfunction "19_19") (pintype "passive"))
    )
    (net (code "28") (name "/P1_31") (class "Default")
      (node (ref "JP10") (pin "3") (pinfunction "3_3") (pintype "passive"))
      (node (ref "LPC1") (pin "20") (pinfunction "20_20") (pintype "passive"))
    )
    (net (code "29") (name "/P2.6") (class "Default")
      (node (ref "JP8") (pin "1") (pinfunction "1_1") (pintype "passive"))
      (node (ref "LPC1") (pin "48") (pinfunction "48_48") (pintype "passive"))
      (node (ref "R52") (pin "2") (pinfunction "2_2") (pintype "passive"))
      (node (ref "R53") (pin "1") (pinfunction "1_1") (pintype "passive"))
    )
    (net (code "30") (name "/P2.7") (class "Default")
      (node (ref "JP8") (pin "4") (pinfunction "4_4") (pintype "passive"))
      (node (ref "LPC1") (pin "49") (pinfunction "49_49") (pintype "passive"))
    )
    (net (code "31") (name "/P2.9") (class "Default")
      (node (ref "LPC1") (pin "55") (pinfunction "55_55") (pintype "passive"))
      (node (ref "Q2") (pin "1") (pinfunction "G_1") (pintype "passive"))
    )
    (net (code "32") (name "/PLAY") (class "Default")
      (node (ref "JP14") (pin "1") (pinfunction "1_1") (pintype "passive"))
      (node (ref "LPC1") (pin "53") (pinfunction "53_53") (pintype "passive"))
      (node (ref "R32") (pin "1") (pinfunction "1_1") (pintype "passive"))
      (node (ref "S2") (pin "1") (pinfunction "1_1") (pintype "passive"))
      (node (ref "S2") (pin "2") (pinfunction "2_2") (pintype "passive"))
    )
    (net (code "33") (name "/PLAY_LED") (class "Default")
      (node (ref "JP15") (pin "2") (pinfunction "2_2") (pintype "passive"))
      (node (ref "LPC1") (pin "59") (pinfunction "59_59") (pintype "passive"))
      (node (ref "PLAY") (pin "A") (pinfunction "A_A") (pintype "passive"))
    )
    (net (code "34") (name "/POT_SCL") (class "Default")
      (node (ref "JP9") (pin "4") (pinfunction "4_4") (pintype "passive"))
      (node (ref "LPC1") (pin "10") (pinfunction "10_10") (pintype "passive"))
    )
    (net (code "35") (name "/POT_SDA") (class "Default")
      (node (ref "JP9") (pin "3") (pinfunction "3_3") (pintype "passive"))
      (node (ref "LPC1") (pin "9") (pinfunction "9_9") (pintype "passive"))
    )
    (net (code "36") (name "/PWM0") (class "Default")
      (node (ref "JP8") (pin "2") (pinfunction "2_2") (pintype "passive"))
      (node (ref "LPC1") (pin "46") (pinfunction "46_46") (pintype "passive"))
      (node (ref "R6") (pin "2") (pinfunction "2_2") (pintype "passive"))
      (node (ref "R7") (pin "1") (pinfunction "1_1") (pintype "passive"))
    )
    (net (code "37") (name "/PWM1") (class "Default")
      (node (ref "IC2") (pin "2") (pinfunction "P$1_2") (pintype "bidirectional"))
      (node (ref "JP8") (pin "3") (pinfunction "3_3") (pintype "passive"))
      (node (ref "LPC1") (pin "47") (pinfunction "47_47") (pintype "passive"))
      (node (ref "R16") (pin "2") (pinfunction "2_2") (pintype "passive"))
    )
    (net (code "38") (name "/PWM1_FET") (class "Default")
      (node (ref "Q3") (pin "G") (pinfunction "G_G") (pintype "passive"))
      (node (ref "R14") (pin "2") (pinfunction "2_2") (pintype "passive"))
      (node (ref "R23") (pin "1") (pinfunction "1_1") (pintype "passive"))
    )
    (net (code "39") (name "/RD+") (class "Default")
      (node (ref "LPC1") (pin "33") (pinfunction "33_33") (pintype "passive"))
      (node (ref "RJ1") (pin "RD+") (pinfunction "RD+_RD+") (pintype "bidirectional"))
    )
    (net (code "40") (name "/RD-") (class "Default")
      (node (ref "LPC1") (pin "32") (pinfunction "32_32") (pintype "passive"))
      (node (ref "RJ1") (pin "RD-") (pinfunction "RD-_RD-") (pintype "bidirectional"))
    )
    (net (code "41") (name "/RESET") (class "Default")
      (node (ref "LPC1") (pin "4") (pinfunction "4_4") (pintype "passive"))
      (node (ref "R1") (pin "1") (pinfunction "1_1") (pintype "passive"))
      (node (ref "R30") (pin "1") (pinfunction "1_1") (pintype "passive"))
      (node (ref "RESET") (pin "1") (pinfunction "1_1") (pintype "passive"))
      (node (ref "RESET") (pin "2") (pinfunction "2_2") (pintype "passive"))
    )
    (net (code "42") (name "/RX_0") (class "Default")
      (node (ref "LPC1") (pin "22") (pinfunction "22_22") (pintype "passive"))
      (node (ref "R4") (pin "2") (pinfunction "2_2") (pintype "passive"))
    )
    (net (code "43") (name "/SCK1") (class "Default")
      (node (ref "JP11") (pin "4") (pinfunction "4_4") (pintype "passive"))
      (node (ref "LPC1") (pin "13") (pinfunction "13_13") (pintype "passive"))
    )
    (net (code "44") (name "/SCL") (class "Default")
      (node (ref "JP12") (pin "4") (pinfunction "4_4") (pintype "passive"))
      (node (ref "LPC1") (pin "26") (pinfunction "26_26") (pintype "passive"))
      (node (ref "R41") (pin "1") (pinfunction "1_1") (pintype "passive"))
    )
    (net (code "45") (name "/SDA") (class "Default")
      (node (ref "JP12") (pin "3") (pinfunction "3_3") (pintype "passive"))
      (node (ref "LPC1") (pin "25") (pinfunction "25_25") (pintype "passive"))
      (node (ref "R42") (pin "1") (pinfunction "1_1") (pintype "passive"))
    )
    (net (code "46") (name "/SD_CD") (class "Default")
      (node (ref "JP6") (pin "3") (pinfunction "3_3") (pintype "passive"))
      (node (ref "LPC1") (pin "52") (pinfunction "52_52") (pintype "passive"))
    )
    (net (code "47") (name "/SD_CS") (class "Default")
      (node (ref "LPC1") (pin "8") (pinfunction "8_8") (pintype "passive"))
      (node (ref "R8") (pin "1") (pinfunction "1_1") (pintype "passive"))
      (node (ref "U1") (pin "2") (pinfunction "CS_2") (pintype "bidirectional"))
    )
    (net (code "48") (name "/SD_IRQ") (class "Default")
      (node (ref "JP6") (pin "1") (pinfunction "1_1") (pintype "passive"))
      (node (ref "LPC1") (pin "61") (pinfunction "61_61") (pintype "passive"))
    )
    (net (code "49") (name "/SD_MISO") (class "Default")
      (node (ref "LPC1") (pin "6") (pinfunction "6_6") (pintype "passive"))
      (node (ref "R9") (pin "1") (pinfunction "1_1") (pintype "passive"))
      (node (ref "U1") (pin "7") (pinfunction "DO_7") (pintype "bidirectional"))
    )
    (net (code "50") (name "/SD_MOSI") (class "Default")
      (node (ref "LPC1") (pin "5") (pinfunction "5_5") (pintype "passive"))
      (node (ref "R10") (pin "1") (pinfunction "1_1") (pintype "passive"))
      (node (ref "U1") (pin "3") (pinfunction "DI_3") (pintype "bidirectional"))
    )
    (net (code "51") (name "/SD_SCK") (class "Default")
      (node (ref "LPC1") (pin "7") (pinfunction "7_7") (pintype "passive"))
      (node (ref "U1") (pin "5") (pinfunction "SCK_5") (pintype "bidirectional"))
    )
    (net (code "52") (name "/SD_WP") (class "Default")
      (node (ref "JP6") (pin "2") (pinfunction "2_2") (pintype "passive"))
      (node (ref "LPC1") (pin "60") (pinfunction "60_60") (pintype "passive"))
    )
    (net (code "53") (name "/SMALL_MOSFET_POWER") (class "Default")
      (node (ref "C1") (pin "A") (pinfunction "+_A") (pintype "passive"))
      (node (ref "R2") (pin "1") (pinfunction "1_1") (pintype "passive"))
      (node (ref "X1") (pin "1") (pinfunction "SK_1") (pintype "passive"))
      (node (ref "X3") (pin "1") (pinfunction "SK_1") (pintype "passive"))
    )
    (net (code "54") (name "/SSEL1") (class "Default")
      (node (ref "JP11") (pin "5") (pinfunction "5_5") (pintype "passive"))
      (node (ref "LPC1") (pin "14") (pinfunction "14_14") (pintype "passive"))
    )
    (net (code "55") (name "/STP1") (class "Default")
      (node (ref "LPC1") (pin "42") (pinfunction "42_42") (pintype "passive"))
      (node (ref "M4") (pin "15") (pinfunction "STEP_15") (pintype "input"))
    )
    (net (code "56") (name "/STP2") (class "Default")
      (node (ref "LPC1") (pin "43") (pinfunction "43_43") (pintype "passive"))
      (node (ref "M3") (pin "15") (pinfunction "STEP_15") (pintype "input"))
    )
    (net (code "57") (name "/STP3") (class "Default")
      (node (ref "JP16") (pin "2") (pinfunction "2_2") (pintype "passive"))
      (node (ref "LPC1") (pin "44") (pinfunction "44_44") (pintype "passive"))
    )
    (net (code "58") (name "/STP4") (class "Default")
      (node (ref "LPC1") (pin "45") (pinfunction "45_45") (pintype "passive"))
      (node (ref "M2") (pin "15") (pinfunction "STEP_15") (pintype "input"))
    )
    (net (code "59") (name "/STP5") (class "Default")
      (node (ref "LPC1") (pin "50") (pinfunction "50_50") (pintype "passive"))
      (node (ref "M1") (pin "15") (pinfunction "STEP_15") (pintype "input"))
    )
    (net (code "60") (name "/TD+") (class "Default")
      (node (ref "LPC1") (pin "35") (pinfunction "35_35") (pintype "passive"))
      (node (ref "RJ1") (pin "TD+") (pinfunction "TD+_TD+") (pintype "bidirectional"))
    )
    (net (code "61") (name "/TD-") (class "Default")
      (node (ref "LPC1") (pin "34") (pinfunction "34_34") (pintype "passive"))
      (node (ref "RJ1") (pin "TD-") (pinfunction "TD-_TD-") (pintype "bidirectional"))
    )
    (net (code "62") (name "/TH1") (class "Default")
      (node (ref "C2") (pin "A") (pinfunction "+_A") (pintype "passive"))
      (node (ref "LPC1") (pin "15") (pinfunction "15_15") (pintype "passive"))
      (node (ref "RN1") (pin "1") (pinfunction "1_1") (pintype "passive"))
      (node (ref "THERM.") (pin "2") (pinfunction "2_2") (pintype "passive"))
    )
    (net (code "63") (name "/TH2") (class "Default")
      (node (ref "C3") (pin "A") (pinfunction "+_A") (pintype "passive"))
      (node (ref "LPC1") (pin "16") (pinfunction "16_16") (pintype "passive"))
      (node (ref "RN1") (pin "2") (pinfunction "1_2") (pintype "passive"))
      (node (ref "THERM.") (pin "4") (pinfunction "4_4") (pintype "passive"))
    )
    (net (code "64") (name "/TH3") (class "Default")
      (node (ref "C4") (pin "A") (pinfunction "+_A") (pintype "passive"))
      (node (ref "LPC1") (pin "17") (pinfunction "17_17") (pintype "passive"))
      (node (ref "RN1") (pin "3") (pinfunction "1_3") (pintype "passive"))
      (node (ref "THERM.") (pin "6") (pinfunction "6_6") (pintype "passive"))
    )
    (net (code "65") (name "/TH4") (class "Default")
      (node (ref "C5") (pin "A") (pinfunction "+_A") (pintype "passive"))
      (node (ref "LPC1") (pin "18") (pinfunction "18_18") (pintype "passive"))
      (node (ref "RN1") (pin "4") (pinfunction "1_4") (pintype "passive"))
      (node (ref "THERM.") (pin "8") (pinfunction "8_8") (pintype "passive"))
    )
    (net (code "66") (name "/TX_0") (class "Default")
      (node (ref "JP5") (pin "3") (pinfunction "3_3") (pintype "passive"))
      (node (ref "LPC1") (pin "21") (pinfunction "21_21") (pintype "passive"))
    )
    (net (code "67") (name "/USB_D+") (class "Default")
      (node (ref "C14") (pin "2") (pinfunction "2_2") (pintype "passive"))
      (node (ref "LPC1") (pin "37") (pinfunction "37_37") (pintype "passive"))
      (node (ref "R17") (pin "1") (pinfunction "1_1") (pintype "passive"))
      (node (ref "R20") (pin "2") (pinfunction "2_2") (pintype "passive"))
    )
    (net (code "68") (name "/USB_D-") (class "Default")
      (node (ref "C13") (pin "2") (pinfunction "2_2") (pintype "passive"))
      (node (ref "LPC1") (pin "36") (pinfunction "36_36") (pintype "passive"))
      (node (ref "R21") (pin "2") (pinfunction "2_2") (pintype "passive"))
    )
    (net (code "69") (name "/VBB") (class "Default")
      (node (ref "C12") (pin "+") (pinfunction "+_+") (pintype "passive"))
      (node (ref "C21") (pin "+") (pinfunction "+_+") (pintype "passive"))
      (node (ref "C25") (pin "+") (pinfunction "+_+") (pintype "passive"))
      (node (ref "C26") (pin "+") (pinfunction "+_+") (pintype "passive"))
      (node (ref "D3") (pin "C") (pinfunction "C_C") (pintype "passive"))
      (node (ref "M1") (pin "8") (pinfunction "VMOT_8") (pintype "power_in"))
      (node (ref "M2") (pin "8") (pinfunction "VMOT_8") (pintype "power_in"))
      (node (ref "M3") (pin "8") (pinfunction "VMOT_8") (pintype "power_in"))
      (node (ref "M4") (pin "8") (pinfunction "VMOT_8") (pintype "power_in"))
      (node (ref "Q5") (pin "S") (pinfunction "S_S") (pintype "passive"))
      (node (ref "R54") (pin "2") (pinfunction "2_2") (pintype "passive"))
    )
    (net (code "70") (name "/VBB_IN") (class "Default")
      (node (ref "Q5") (pin "D") (pinfunction "D_D") (pintype "passive"))
      (node (ref "X7") (pin "2") (pinfunction "SK_2") (pintype "passive"))
    )
    (net (code "71") (name "/X_MAX") (class "Default")
      (node (ref "C16") (pin "1") (pinfunction "1_1") (pintype "passive"))
      (node (ref "LPC1") (pin "66") (pinfunction "66_66") (pintype "passive"))
      (node (ref "R25") (pin "2") (pinfunction "2_2") (pintype "passive"))
    )
    (net (code "72") (name "/X_MIN") (class "Default")
      (node (ref "C15") (pin "1") (pinfunction "1_1") (pintype "passive"))
      (node (ref "LPC1") (pin "67") (pinfunction "67_67") (pintype "passive"))
      (node (ref "R22") (pin "2") (pinfunction "2_2") (pintype "passive"))
    )
    (net (code "73") (name "/Y_MAX") (class "Default")
      (node (ref "C18") (pin "1") (pinfunction "1_1") (pintype "passive"))
      (node (ref "LPC1") (pin "64") (pinfunction "64_64") (pintype "passive"))
      (node (ref "R36") (pin "2") (pinfunction "2_2") (pintype "passive"))
    )
    (net (code "74") (name "/Y_MIN") (class "Default")
      (node (ref "C17") (pin "1") (pinfunction "1_1") (pintype "passive"))
      (node (ref "LPC1") (pin "65") (pinfunction "65_65") (pintype "passive"))
      (node (ref "R28") (pin "2") (pinfunction "2_2") (pintype "passive"))
    )
    (net (code "75") (name "/Z_MAX") (class "Default")
      (node (ref "C20") (pin "1") (pinfunction "1_1") (pintype "passive"))
      (node (ref "LPC1") (pin "62") (pinfunction "62_62") (pintype "passive"))
      (node (ref "R45") (pin "2") (pinfunction "2_2") (pintype "passive"))
    )
    (net (code "76") (name "/Z_MIN") (class "Default")
      (node (ref "C19") (pin "1") (pinfunction "1_1") (pintype "passive"))
      (node (ref "LPC1") (pin "63") (pinfunction "63_63") (pintype "passive"))
      (node (ref "R43") (pin "2") (pinfunction "2_2") (pintype "passive"))
    )
    (net (code "77") (name "3.3V") (class "Default")
      (node (ref "C7") (pin "2") (pinfunction "2_2") (pintype "passive"))
      (node (ref "C8") (pin "2") (pinfunction "2_2") (pintype "passive"))
      (node (ref "C9") (pin "P$1") (pinfunction "+_P$1") (pintype "passive"))
      (node (ref "D1") (pin "C") (pinfunction "C_C") (pintype "passive"))
      (node (ref "FB1") (pin "2") (pinfunction "P$2_2") (pintype "bidirectional"))
      (node (ref "JP11") (pin "6") (pinfunction "6_6") (pintype "passive"))
      (node (ref "JP12") (pin "1") (pinfunction "1_1") (pintype "passive"))
      (node (ref "JP13") (pin "1") (pinfunction "1_1") (pintype "passive"))
      (node (ref "JP7") (pin "1") (pinfunction "1_1") (pintype "passive"))
      (node (ref "JP9") (pin "1") (pinfunction "1_1") (pintype "passive"))
      (node (ref "L1") (pin "2") (pinfunction "2_2") (pintype "passive"))
      (node (ref "LPC1") (pin "28") (pinfunction "28_28") (pintype "passive"))
      (node (ref "MS1") (pin "2") (pinfunction "2_2") (pintype "passive"))
      (node (ref "MS2") (pin "2") (pinfunction "2_2") (pintype "passive"))
      (node (ref "MS3") (pin "2") (pinfunction "2_2") (pintype "passive"))
      (node (ref "Q2") (pin "2") (pinfunction "S_2") (pintype "passive"))
      (node (ref "R10") (pin "2") (pinfunction "2_2") (pintype "passive"))
      (node (ref "R11") (pin "2") (pinfunction "2_2") (pintype "passive"))
      (node (ref "R12") (pin "2") (pinfunction "2_2") (pintype "passive"))
      (node (ref "R30") (pin "2") (pinfunction "2_2") (pintype "passive"))
      (node (ref "R31") (pin "2") (pinfunction "2_2") (pintype "passive"))
      (node (ref "R32") (pin "2") (pinfunction "2_2") (pintype "passive"))
      (node (ref "R33") (pin "2") (pinfunction "2_2") (pintype "passive"))
      (node (ref "R38") (pin "2") (pinfunction "2_2") (pintype "passive"))
      (node (ref "R39") (pin "2") (pinfunction "2_2") (pintype "passive"))
      (node (ref "R46") (pin "2") (pinfunction "2_2") (pintype "passive"))
      (node (ref "R47") (pin "2") (pinfunction "2_2") (pintype "passive"))
      (node (ref "R48") (pin "2") (pinfunction "2_2") (pintype "passive"))
      (node (ref "R49") (pin "2") (pinfunction "2_2") (pintype "passive"))
      (node (ref "R50") (pin "2") (pinfunction "2_2") (pintype "passive"))
      (node (ref "R8") (pin "2") (pinfunction "2_2") (pintype "passive"))
      (node (ref "R9") (pin "2") (pinfunction "2_2") (pintype "passive"))
      (node (ref "SJ1") (pin "1") (pinfunction "1_1") (pintype "passive"))
      (node (ref "U1") (pin "4") (pinfunction "VCC_4") (pintype "bidirectional"))
      (node (ref "X2") (pin "1") (pinfunction "S_1") (pintype "passive"))
      (node (ref "X2") (pin "11") (pinfunction "S_11") (pintype "passive"))
      (node (ref "X2") (pin "2") (pinfunction "S_2") (pintype "passive"))
    )
    (net (code "78") (name "5V") (class "Default")
      (node (ref "JP13") (pin "3") (pinfunction "3_3") (pintype "passive"))
      (node (ref "JP7") (pin "3") (pinfunction "3_3") (pintype "passive"))
      (node (ref "LPC1") (pin "2") (pinfunction "2_2") (pintype "passive"))
      (node (ref "SJ1") (pin "3") (pinfunction "3_3") (pintype "passive"))
    )
    (net (code "79") (name "GND") (class "Default")
      (node (ref "ATX") (pin "C") (pinfunction "C_C") (pintype "passive"))
      (node (ref "C1") (pin "C") (pinfunction "-_C") (pintype "passive"))
      (node (ref "C10") (pin "-") (pinfunction "-_-") (pintype "passive"))
      (node (ref "C11") (pin "1") (pinfunction "1_1") (pintype "passive"))
      (node (ref "C12") (pin "-") (pinfunction "-_-") (pintype "passive"))
      (node (ref "C13") (pin "1") (pinfunction "1_1") (pintype "passive"))
      (node (ref "C14") (pin "1") (pinfunction "1_1") (pintype "passive"))
      (node (ref "C15") (pin "2") (pinfunction "2_2") (pintype "passive"))
      (node (ref "C16") (pin "2") (pinfunction "2_2") (pintype "passive"))
      (node (ref "C17") (pin "2") (pinfunction "2_2") (pintype "passive"))
      (node (ref "C18") (pin "2") (pinfunction "2_2") (pintype "passive"))
      (node (ref "C19") (pin "2") (pinfunction "2_2") (pintype "passive"))
      (node (ref "C2") (pin "C") (pinfunction "-_C") (pintype "passive"))
      (node (ref "C20") (pin "2") (pinfunction "2_2") (pintype "passive"))
      (node (ref "C21") (pin "-") (pinfunction "-_-") (pintype "passive"))
      (node (ref "C22") (pin "2") (pinfunction "2_2") (pintype "passive"))
      (node (ref "C23") (pin "C") (pinfunction "-_C") (pintype "passive"))
      (node (ref "C24") (pin "1") (pinfunction "1_1") (pintype "passive"))
      (node (ref "C25") (pin "-") (pinfunction "-_-") (pintype "passive"))
      (node (ref "C26") (pin "-") (pinfunction "-_-") (pintype "passive"))
      (node (ref "C3") (pin "C") (pinfunction "-_C") (pintype "passive"))
      (node (ref "C4") (pin "C") (pinfunction "-_C") (pintype "passive"))
      (node (ref "C5") (pin "C") (pinfunction "-_C") (pintype "passive"))
      (node (ref "C6") (pin "1") (pinfunction "1_1") (pintype "passive"))
      (node (ref "C7") (pin "1") (pinfunction "1_1") (pintype "passive"))
      (node (ref "C8") (pin "1") (pinfunction "1_1") (pintype "passive"))
      (node (ref "C9") (pin "P$2") (pinfunction "-_P$2") (pintype "passive"))
      (node (ref "D2") (pin "A") (pinfunction "A_A") (pintype "passive"))
      (node (ref "FLOW") (pin "2") (pinfunction "S_2") (pintype "passive"))
      (node (ref "IC1") (pin "3") (pinfunction "GND_3") (pintype "power_in"))
      (node (ref "IC2") (pin "3") (pinfunction "P$2_3") (pintype "bidirectional"))
      (node (ref "JP10") (pin "5") (pinfunction "5_5") (pintype "passive"))
      (node (ref "JP11") (pin "1") (pinfunction "1_1") (pintype "passive"))
      (node (ref "JP12") (pin "2") (pinfunction "2_2") (pintype "passive"))
      (node (ref "JP14") (pin "2") (pinfunction "2_2") (pintype "passive"))
      (node (ref "JP16") (pin "4") (pinfunction "4_4") (pintype "passive"))
      (node (ref "JP5") (pin "1") (pinfunction "1_1") (pintype "passive"))
      (node (ref "JP7") (pin "2") (pinfunction "2_2") (pintype "passive"))
      (node (ref "JP8") (pin "5") (pinfunction "5_5") (pintype "passive"))
      (node (ref "JP9") (pin "2") (pinfunction "2_2") (pintype "passive"))
      (node (ref "LED1") (pin "C") (pinfunction "C_C") (pintype "passive"))
      (node (ref "LED2") (pin "C") (pinfunction "C_C") (pintype "passive"))
      (node (ref "LED3") (pin "C") (pinfunction "C_C") (pintype "passive"))
      (node (ref "LED4") (pin "C") (pinfunction "C_C") (pintype "passive"))
      (node (ref "LEDS") (pin "2") (pinfunction "2_2") (pintype "passive"))
      (node (ref "LEDS") (pin "4") (pinfunction "4_4") (pintype "passive"))
      (node (ref "LEDS") (pin "6") (pinfunction "6_6") (pintype "passive"))
      (node (ref "LEDS") (pin "8") (pinfunction "8_8") (pintype "passive"))
      (node (ref "LPC1") (pin "1") (pinfunction "1_1") (pintype "passive"))
      (node (ref "LPC1") (pin "54") (pinfunction "54_54") (pintype "passive"))
      (node (ref "M1") (pin "1") (pinfunction "GND_1") (pintype "power_in"))
      (node (ref "M1") (pin "7") (pinfunction "GND_7") (pintype "power_in"))
      (node (ref "M2") (pin "1") (pinfunction "GND_1") (pintype "power_in"))
      (node (ref "M2") (pin "7") (pinfunction "GND_7") (pintype "power_in"))
      (node (ref "M3") (pin "1") (pinfunction "GND_1") (pintype "power_in"))
      (node (ref "M3") (pin "7") (pinfunction "GND_7") (pintype "power_in"))
      (node (ref "M4") (pin "1") (pinfunction "GND_1") (pintype "power_in"))
      (node (ref "M4") (pin "7") (pinfunction "GND_7") (pintype "power_in"))
      (node (ref "PS_ON") (pin "2") (pinfunction "2_2") (pintype "passive"))
      (node (ref "Q1") (pin "3") (pinfunction "S_3") (pintype "passive"))
      (node (ref "Q3") (pin "S") (pinfunction "S_S") (pintype "passive"))
      (node (ref "Q4") (pin "3") (pinfunction "S_3") (pintype "passive"))
      (node (ref "R15") (pin "1") (pinfunction "1_1") (pintype "passive"))
      (node (ref "R16") (pin "1") (pinfunction "1_1") (pintype "passive"))
      (node (ref "R23") (pin "2") (pinfunction "2_2") (pintype "passive"))
      (node (ref "R5") (pin "1") (pinfunction "1_1") (pintype "passive"))
      (node (ref "R53") (pin "2") (pinfunction "2_2") (pintype "passive"))
      (node (ref "R55") (pin "2") (pinfunction "2_2") (pintype "passive"))
      (node (ref "R7") (pin "2") (pinfunction "2_2") (pintype "passive"))
      (node (ref "RESET") (pin "3") (pinfunction "3_3") (pintype "passive"))
      (node (ref "RESET") (pin "4") (pinfunction "4_4") (pintype "passive"))
      (node (ref "RJ1") (pin "G+") (pinfunction "G+_G+") (pintype "bidirectional"))
      (node (ref "RJ1") (pin "G-") (pinfunction "G-_G-") (pintype "bidirectional"))
      (node (ref "RJ1") (pin "GND") (pinfunction "GND_GND") (pintype "bidirectional"))
      (node (ref "RJ1") (pin "SHIELD0") (pinfunction "SHIELD0_SHIELD0") (pintype "bidirectional"))
      (node (ref "RJ1") (pin "SHIELD1") (pinfunction "SHIELD1_SHIELD1") (pintype "bidirectional"))
      (node (ref "RJ1") (pin "Y+") (pinfunction "Y+_Y+") (pintype "bidirectional"))
      (node (ref "RJ1") (pin "Y-") (pinfunction "Y-_Y-") (pintype "bidirectional"))
      (node (ref "S1") (pin "3") (pinfunction "3_3") (pintype "passive"))
      (node (ref "S1") (pin "4") (pinfunction "4_4") (pintype "passive"))
      (node (ref "S2") (pin "3") (pinfunction "3_3") (pintype "passive"))
      (node (ref "S2") (pin "4") (pinfunction "4_4") (pintype "passive"))
      (node (ref "THERM.") (pin "1") (pinfunction "1_1") (pintype "passive"))
      (node (ref "THERM.") (pin "3") (pinfunction "3_3") (pintype "passive"))
      (node (ref "THERM.") (pin "5") (pinfunction "5_5") (pintype "passive"))
      (node (ref "THERM.") (pin "7") (pinfunction "7_7") (pintype "passive"))
      (node (ref "U1") (pin "6") (pinfunction "GND_6") (pintype "bidirectional"))
      (node (ref "U1") (pin "CD1") (pinfunction "SHIELD_CD1") (pintype "bidirectional"))
      (node (ref "U1") (pin "CD2") (pinfunction "SHIELD_CD2") (pintype "bidirectional"))
      (node (ref "U1") (pin "GND1") (pinfunction "SHIELD_GND1") (pintype "bidirectional"))
      (node (ref "U1") (pin "GND3") (pinfunction "SHIELD_GND3") (pintype "bidirectional"))
      (node (ref "USB") (pin "C") (pinfunction "C_C") (pintype "passive"))
      (node (ref "VBB") (pin "C") (pinfunction "C_C") (pintype "passive"))
      (node (ref "X1") (pin "2") (pinfunction "SK_2") (pintype "passive"))
      (node (ref "X2") (pin "13") (pinfunction "S_13") (pintype "passive"))
      (node (ref "X2") (pin "15") (pinfunction "S_15") (pintype "passive"))
      (node (ref "X2") (pin "16") (pinfunction "S_16") (pintype "passive"))
      (node (ref "X2") (pin "17") (pinfunction "S_17") (pintype "passive"))
      (node (ref "X2") (pin "3") (pinfunction "S_3") (pintype "passive"))
      (node (ref "X2") (pin "5") (pinfunction "S_5") (pintype "passive"))
      (node (ref "X2") (pin "7") (pinfunction "S_7") (pintype "passive"))
      (node (ref "X4") (pin "2") (pinfunction "SK_2") (pintype "passive"))
      (node (ref "X6") (pin "GND") (pinfunction "GND_GND") (pintype "bidirectional"))
      (node (ref "X7") (pin "1") (pinfunction "SK_1") (pintype "passive"))
      (node (ref "XMAX") (pin "2") (pinfunction "2_2") (pintype "passive"))
      (node (ref "XMIN") (pin "2") (pinfunction "2_2") (pintype "passive"))
      (node (ref "YMAX") (pin "2") (pinfunction "2_2") (pintype "passive"))
      (node (ref "YMIN") (pin "2") (pinfunction "2_2") (pintype "passive"))
      (node (ref "ZMAX") (pin "2") (pinfunction "2_2") (pintype "passive"))
      (node (ref "ZMIN") (pin "2") (pinfunction "2_2") (pintype "passive"))
    )
    (net (code "80") (name "Net-(ATX-PadA)") (class "Default")
      (node (ref "ATX") (pin "A") (pinfunction "A_A") (pintype "passive"))
      (node (ref "R3") (pin "1") (pinfunction "1_1") (pintype "passive"))
    )
    (net (code "81") (name "Net-(BIG-PadA)") (class "Default")
      (node (ref "BIG") (pin "A") (pinfunction "A_A") (pintype "passive"))
      (node (ref "R13") (pin "2") (pinfunction "2_2") (pintype "passive"))
    )
    (net (code "82") (name "Net-(D3-PadA)") (class "Default")
      (node (ref "D3") (pin "A") (pinfunction "A_A") (pintype "passive"))
      (node (ref "Q5") (pin "G") (pinfunction "G_G") (pintype "passive"))
      (node (ref "R55") (pin "1") (pinfunction "1_1") (pintype "passive"))
    )
    (net (code "83") (name "Net-(FAN-PadA)") (class "Default")
      (node (ref "FAN") (pin "A") (pinfunction "A_A") (pintype "passive"))
      (node (ref "R51") (pin "2") (pinfunction "2_2") (pintype "passive"))
    )
    (net (code "84") (name "Net-(FB1-P$1)") (class "Default")
      (node (ref "C24") (pin "2") (pinfunction "2_2") (pintype "passive"))
      (node (ref "FB1") (pin "1") (pinfunction "P$1_1") (pintype "bidirectional"))
      (node (ref "RJ1") (pin "P4") (pinfunction "P4_P4") (pintype "bidirectional"))
      (node (ref "RJ1") (pin "P5") (pinfunction "P5_P5") (pintype "bidirectional"))
    )
    (net (code "85") (name "Net-(IC1A-I)") (class "Default")
      (node (ref "IC1") (pin "2") (pinfunction "I_2") (pintype "input"))
      (node (ref "X2") (pin "8") (pinfunction "S_8") (pintype "passive"))
    )
    (net (code "86") (name "Net-(IC1A-O)") (class "Default")
      (node (ref "IC1") (pin "4") (pinfunction "O_4") (pintype "open_collector"))
      (node (ref "R1") (pin "2") (pinfunction "2_2") (pintype "passive"))
    )
    (net (code "87") (name "Net-(IC1B-VCC)") (class "Default")
      (node (ref "C6") (pin "2") (pinfunction "2_2") (pintype "passive"))
      (node (ref "IC1") (pin "5") (pinfunction "VCC_5") (pintype "power_in"))
      (node (ref "R3") (pin "2") (pinfunction "2_2") (pintype "passive"))
      (node (ref "X2") (pin "9") (pinfunction "S_9") (pintype "passive"))
    )
    (net (code "88") (name "Net-(IC2A-P$2)") (class "Default")
      (node (ref "IC2") (pin "7") (pinfunction "P$2_7") (pintype "bidirectional"))
      (node (ref "R14") (pin "1") (pinfunction "1_1") (pintype "passive"))
    )
    (net (code "89") (name "Net-(IC2B-P$1)") (class "Default")
      (node (ref "IC2") (pin "4") (pinfunction "P$1_4") (pintype "bidirectional"))
      (node (ref "R15") (pin "2") (pinfunction "2_2") (pintype "passive"))
    )
    (net (code "90") (name "Net-(J4A-S)") (class "Default")
      (node (ref "FAN") (pin "C") (pinfunction "C_C") (pintype "passive"))
      (node (ref "J4") (pin "1") (pinfunction "S_1") (pintype "passive"))
      (node (ref "Q4") (pin "4") (pinfunction "D_4") (pintype "passive"))
    )
    (net (code "91") (name "Net-(JP5-Pad2)") (class "Default")
      (node (ref "JP5") (pin "2") (pinfunction "2_2") (pintype "passive"))
      (node (ref "R4") (pin "1") (pinfunction "1_1") (pintype "passive"))
      (node (ref "R5") (pin "2") (pinfunction "2_2") (pintype "passive"))
    )
    (net (code "92") (name "Net-(JP7-Pad4)") (class "Default")
      (node (ref "JP7") (pin "4") (pinfunction "4_4") (pintype "passive"))
      (node (ref "LPC1") (pin "3") (pinfunction "3_3") (pintype "passive"))
    )
    (net (code "93") (name "Net-(JP13-Pad2)") (class "Default")
      (node (ref "JP13") (pin "2") (pinfunction "2_2") (pintype "passive"))
      (node (ref "R19") (pin "2") (pinfunction "2_2") (pintype "passive"))
      (node (ref "R24") (pin "2") (pinfunction "2_2") (pintype "passive"))
      (node (ref "R27") (pin "2") (pinfunction "2_2") (pintype "passive"))
      (node (ref "R34") (pin "2") (pinfunction "2_2") (pintype "passive"))
      (node (ref "R40") (pin "2") (pinfunction "2_2") (pintype "passive"))
      (node (ref "R44") (pin "2") (pinfunction "2_2") (pintype "passive"))
      (node (ref "XMAX") (pin "3") (pinfunction "3_3") (pintype "passive"))
      (node (ref "XMIN") (pin "3") (pinfunction "3_3") (pintype "passive"))
      (node (ref "YMAX") (pin "3") (pinfunction "3_3") (pintype "passive"))
      (node (ref "YMIN") (pin "3") (pinfunction "3_3") (pintype "passive"))
      (node (ref "ZMAX") (pin "3") (pinfunction "3_3") (pintype "passive"))
      (node (ref "ZMIN") (pin "3") (pinfunction "3_3") (pintype "passive"))
    )
    (net (code "94") (name "Net-(JP15-Pad1)") (class "Default")
      (node (ref "JP15") (pin "1") (pinfunction "1_1") (pintype "passive"))
      (node (ref "PLAY") (pin "C") (pinfunction "C_C") (pintype "passive"))
      (node (ref "R33") (pin "1") (pinfunction "1_1") (pintype "passive"))
    )
    (net (code "95") (name "Net-(LED1-PadA)") (class "Default")
      (node (ref "LED1") (pin "A") (pinfunction "A_A") (pintype "passive"))
      (node (ref "R26") (pin "1") (pinfunction "1_1") (pintype "passive"))
    )
    (net (code "96") (name "Net-(LED2-PadA)") (class "Default")
      (node (ref "LED2") (pin "A") (pinfunction "A_A") (pintype "passive"))
      (node (ref "R29") (pin "1") (pinfunction "1_1") (pintype "passive"))
    )
    (net (code "97") (name "Net-(LED3-PadA)") (class "Default")
      (node (ref "LED3") (pin "A") (pinfunction "A_A") (pintype "passive"))
      (node (ref "R35") (pin "1") (pinfunction "1_1") (pintype "passive"))
    )
    (net (code "98") (name "Net-(LED4-PadA)") (class "Default")
      (node (ref "LED4") (pin "A") (pinfunction "A_A") (pintype "passive"))
      (node (ref "R37") (pin "1") (pinfunction "1_1") (pintype "passive"))
    )
    (net (code "99") (name "Net-(M1-A1)") (class "Default")
      (node (ref "M1") (pin "4") (pinfunction "A1_4") (pintype "output"))
      (node (ref "STEPPER1") (pin "2") (pinfunction "S_2") (pintype "passive"))
    )
    (net (code "100") (name "Net-(M1-A2)") (class "Default")
      (node (ref "M1") (pin "3") (pinfunction "A2_3") (pintype "output"))
      (node (ref "STEPPER1") (pin "1") (pinfunction "S_1") (pintype "passive"))
    )
    (net (code "101") (name "Net-(M1-B1)") (class "Default")
      (node (ref "M1") (pin "5") (pinfunction "B1_5") (pintype "output"))
      (node (ref "STEPPER1") (pin "3") (pinfunction "S_3") (pintype "passive"))
    )
    (net (code "102") (name "Net-(M1-B2)") (class "Default")
      (node (ref "M1") (pin "6") (pinfunction "B2_6") (pintype "output"))
      (node (ref "STEPPER1") (pin "4") (pinfunction "S_4") (pintype "passive"))
    )
    (net (code "103") (name "Net-(M1-{slash}RESET)") (class "Default")
      (node (ref "M1") (pin "13") (pinfunction "/RESET_13") (pintype "input"))
      (node (ref "R12") (pin "1") (pinfunction "1_1") (pintype "passive"))
    )
    (net (code "104") (name "Net-(M1-{slash}SLEEP)") (class "Default")
      (node (ref "M1") (pin "14") (pinfunction "/SLEEP_14") (pintype "input"))
      (node (ref "R11") (pin "1") (pinfunction "1_1") (pintype "passive"))
    )
    (net (code "105") (name "Net-(M2-A1)") (class "Default")
      (node (ref "M2") (pin "4") (pinfunction "A1_4") (pintype "output"))
      (node (ref "STEPPER2") (pin "2") (pinfunction "S_2") (pintype "passive"))
    )
    (net (code "106") (name "Net-(M2-A2)") (class "Default")
      (node (ref "M2") (pin "3") (pinfunction "A2_3") (pintype "output"))
      (node (ref "STEPPER2") (pin "1") (pinfunction "S_1") (pintype "passive"))
    )
    (net (code "107") (name "Net-(M2-B1)") (class "Default")
      (node (ref "M2") (pin "5") (pinfunction "B1_5") (pintype "output"))
      (node (ref "STEPPER2") (pin "3") (pinfunction "S_3") (pintype "passive"))
    )
    (net (code "108") (name "Net-(M2-B2)") (class "Default")
      (node (ref "M2") (pin "6") (pinfunction "B2_6") (pintype "output"))
      (node (ref "STEPPER2") (pin "4") (pinfunction "S_4") (pintype "passive"))
    )
    (net (code "109") (name "Net-(M2-{slash}RESET)") (class "Default")
      (node (ref "M2") (pin "13") (pinfunction "/RESET_13") (pintype "input"))
      (node (ref "R39") (pin "1") (pinfunction "1_1") (pintype "passive"))
    )
    (net (code "110") (name "Net-(M2-{slash}SLEEP)") (class "Default")
      (node (ref "M2") (pin "14") (pinfunction "/SLEEP_14") (pintype "input"))
      (node (ref "R38") (pin "1") (pinfunction "1_1") (pintype "passive"))
    )
    (net (code "111") (name "Net-(M3-A1)") (class "Default")
      (node (ref "M3") (pin "4") (pinfunction "A1_4") (pintype "output"))
      (node (ref "STEPPER3") (pin "2") (pinfunction "S_2") (pintype "passive"))
    )
    (net (code "112") (name "Net-(M3-A2)") (class "Default")
      (node (ref "M3") (pin "3") (pinfunction "A2_3") (pintype "output"))
      (node (ref "STEPPER3") (pin "1") (pinfunction "S_1") (pintype "passive"))
    )
    (net (code "113") (name "Net-(M3-B1)") (class "Default")
      (node (ref "M3") (pin "5") (pinfunction "B1_5") (pintype "output"))
      (node (ref "STEPPER3") (pin "3") (pinfunction "S_3") (pintype "passive"))
    )
    (net (code "114") (name "Net-(M3-B2)") (class "Default")
      (node (ref "M3") (pin "6") (pinfunction "B2_6") (pintype "output"))
      (node (ref "STEPPER3") (pin "4") (pinfunction "S_4") (pintype "passive"))
    )
    (net (code "115") (name "Net-(M3-{slash}RESET)") (class "Default")
      (node (ref "M3") (pin "13") (pinfunction "/RESET_13") (pintype "input"))
      (node (ref "R48") (pin "1") (pinfunction "1_1") (pintype "passive"))
    )
    (net (code "116") (name "Net-(M3-{slash}SLEEP)") (class "Default")
      (node (ref "M3") (pin "14") (pinfunction "/SLEEP_14") (pintype "input"))
      (node (ref "R47") (pin "1") (pinfunction "1_1") (pintype "passive"))
    )
    (net (code "117") (name "Net-(M4-A1)") (class "Default")
      (node (ref "M4") (pin "4") (pinfunction "A1_4") (pintype "output"))
      (node (ref "STEPPER4") (pin "2") (pinfunction "S_2") (pintype "passive"))
    )
    (net (code "118") (name "Net-(M4-A2)") (class "Default")
      (node (ref "M4") (pin "3") (pinfunction "A2_3") (pintype "output"))
      (node (ref "STEPPER4") (pin "1") (pinfunction "S_1") (pintype "passive"))
    )
    (net (code "119") (name "Net-(M4-B1)") (class "Default")
      (node (ref "M4") (pin "5") (pinfunction "B1_5") (pintype "output"))
      (node (ref "STEPPER4") (pin "3") (pinfunction "S_3") (pintype "passive"))
    )
    (net (code "120") (name "Net-(M4-B2)") (class "Default")
      (node (ref "M4") (pin "6") (pinfunction "B2_6") (pintype "output"))
      (node (ref "STEPPER4") (pin "4") (pinfunction "S_4") (pintype "passive"))
    )
    (net (code "121") (name "Net-(M4-{slash}RESET)") (class "Default")
      (node (ref "M4") (pin "13") (pinfunction "/RESET_13") (pintype "input"))
      (node (ref "R50") (pin "1") (pinfunction "1_1") (pintype "passive"))
    )
    (net (code "122") (name "Net-(M4-{slash}SLEEP)") (class "Default")
      (node (ref "M4") (pin "14") (pinfunction "/SLEEP_14") (pintype "input"))
      (node (ref "R49") (pin "1") (pinfunction "1_1") (pintype "passive"))
    )
    (net (code "123") (name "Net-(Q1-D)") (class "Default")
      (node (ref "Q1") (pin "4") (pinfunction "D_4") (pintype "passive"))
      (node (ref "SMALL") (pin "C") (pinfunction "C_C") (pintype "passive"))
      (node (ref "X3") (pin "2") (pinfunction "SK_2") (pintype "passive"))
    )
    (net (code "124") (name "Net-(Q1-G)") (class "Default")
      (node (ref "Q1") (pin "1") (pinfunction "G_1") (pintype "passive"))
      (node (ref "R6") (pin "1") (pinfunction "1_1") (pintype "passive"))
    )
    (net (code "125") (name "Net-(Q2-D)") (class "Default")
      (node (ref "Q2") (pin "3") (pinfunction "D_3") (pintype "passive"))
      (node (ref "R17") (pin "2") (pinfunction "2_2") (pintype "passive"))
    )
    (net (code "126") (name "Net-(Q4-G)") (class "Default")
      (node (ref "Q4") (pin "1") (pinfunction "G_1") (pintype "passive"))
      (node (ref "R52") (pin "1") (pinfunction "1_1") (pintype "passive"))
    )
    (net (code "127") (name "Net-(R2-Pad2)") (class "Default")
      (node (ref "R2") (pin "2") (pinfunction "2_2") (pintype "passive"))
      (node (ref "SMALL") (pin "A") (pinfunction "A_A") (pintype "passive"))
    )
    (net (code "128") (name "Net-(R18-Pad1)") (class "Default")
      (node (ref "R18") (pin "1") (pinfunction "1_1") (pintype "passive"))
      (node (ref "USB") (pin "A") (pinfunction "A_A") (pintype "passive"))
    )
    (net (code "129") (name "Net-(R19-Pad1)") (class "Default")
      (node (ref "R19") (pin "1") (pinfunction "1_1") (pintype "passive"))
      (node (ref "R22") (pin "1") (pinfunction "1_1") (pintype "passive"))
      (node (ref "XMIN") (pin "1") (pinfunction "1_1") (pintype "passive"))
    )
    (net (code "130") (name "Net-(R20-Pad1)") (class "Default")
      (node (ref "R20") (pin "1") (pinfunction "1_1") (pintype "passive"))
      (node (ref "X6") (pin "D+") (pinfunction "D+_D+") (pintype "bidirectional"))
    )
    (net (code "131") (name "Net-(R21-Pad1)") (class "Default")
      (node (ref "R21") (pin "1") (pinfunction "1_1") (pintype "passive"))
      (node (ref "X6") (pin "D-") (pinfunction "D-_D-") (pintype "bidirectional"))
    )
    (net (code "132") (name "Net-(R24-Pad1)") (class "Default")
      (node (ref "R24") (pin "1") (pinfunction "1_1") (pintype "passive"))
      (node (ref "R25") (pin "1") (pinfunction "1_1") (pintype "passive"))
      (node (ref "XMAX") (pin "1") (pinfunction "1_1") (pintype "passive"))
    )
    (net (code "133") (name "Net-(R27-Pad1)") (class "Default")
      (node (ref "R27") (pin "1") (pinfunction "1_1") (pintype "passive"))
      (node (ref "R28") (pin "1") (pinfunction "1_1") (pintype "passive"))
      (node (ref "YMIN") (pin "1") (pinfunction "1_1") (pintype "passive"))
    )
    (net (code "134") (name "Net-(R34-Pad1)") (class "Default")
      (node (ref "R34") (pin "1") (pinfunction "1_1") (pintype "passive"))
      (node (ref "R36") (pin "1") (pinfunction "1_1") (pintype "passive"))
      (node (ref "YMAX") (pin "1") (pinfunction "1_1") (pintype "passive"))
    )
    (net (code "135") (name "Net-(R40-Pad1)") (class "Default")
      (node (ref "R40") (pin "1") (pinfunction "1_1") (pintype "passive"))
      (node (ref "R43") (pin "1") (pinfunction "1_1") (pintype "passive"))
      (node (ref "ZMIN") (pin "1") (pinfunction "1_1") (pintype "passive"))
    )
    (net (code "136") (name "Net-(R41-Pad2)") (class "Default")
      (node (ref "R41") (pin "2") (pinfunction "2_2") (pintype "passive"))
      (node (ref "R42") (pin "2") (pinfunction "2_2") (pintype "passive"))
      (node (ref "SJ1") (pin "2") (pinfunction "2_2") (pintype "passive"))
    )
    (net (code "137") (name "Net-(R44-Pad1)") (class "Default")
      (node (ref "R44") (pin "1") (pinfunction "1_1") (pintype "passive"))
      (node (ref "R45") (pin "1") (pinfunction "1_1") (pintype "passive"))
      (node (ref "ZMAX") (pin "1") (pinfunction "1_1") (pintype "passive"))
    )
    (net (code "138") (name "Net-(R54-Pad1)") (class "Default")
      (node (ref "R54") (pin "1") (pinfunction "1_1") (pintype "passive"))
      (node (ref "VBB") (pin "A") (pinfunction "A_A") (pintype "passive"))
    )
    (net (code "139") (name "Net-(X2F-S)") (class "Default")
      (node (ref "PS_ON") (pin "1") (pinfunction "1_1") (pintype "passive"))
      (node (ref "X2") (pin "14") (pinfunction "S_14") (pintype "passive"))
    )
    (net (code "140") (name "Net-(X5B-SK)") (class "Default")
      (node (ref "BIG") (pin "C") (pinfunction "C_C") (pintype "passive"))
      (node (ref "Q3") (pin "D") (pinfunction "D_D") (pintype "passive"))
      (node (ref "X5") (pin "2") (pinfunction "SK_2") (pintype "passive"))
    )
    (net (code "141") (name "VUSB") (class "Default")
      (node (ref "R18") (pin "2") (pinfunction "2_2") (pintype "passive"))
      (node (ref "X6") (pin "VBUS") (pinfunction "VBUS_VBUS") (pintype "bidirectional"))
    )
    (net (code "142") (name "unconnected-(H1-MOUNT-PadB3,2)") (class "Default")
      (node (ref "H1") (pin "B3,2") (pinfunction "MOUNT_B3,2") (pintype "passive"))
    )
    (net (code "143") (name "unconnected-(H2-MOUNT-PadB3,2)") (class "Default")
      (node (ref "H2") (pin "B3,2") (pinfunction "MOUNT_B3,2") (pintype "passive"))
    )
    (net (code "144") (name "unconnected-(H3-MOUNT-PadB3,2)") (class "Default")
      (node (ref "H3") (pin "B3,2") (pinfunction "MOUNT_B3,2") (pintype "passive"))
    )
    (net (code "145") (name "unconnected-(H4-MOUNT-PadB3,2)") (class "Default")
      (node (ref "H4") (pin "B3,2") (pinfunction "MOUNT_B3,2") (pintype "passive"))
    )
    (net (code "146") (name "unconnected-(IC2B-P$2-Pad5)") (class "Default")
      (node (ref "IC2") (pin "5") (pinfunction "P$2_5") (pintype "bidirectional"))
    )
    (net (code "147") (name "unconnected-(LPC1-Pad29)") (class "Default")
      (node (ref "LPC1") (pin "29") (pinfunction "29_29") (pintype "passive"))
    )
    (net (code "148") (name "unconnected-(LPC1-Pad30)") (class "Default")
      (node (ref "LPC1") (pin "30") (pinfunction "30_30") (pintype "passive"))
    )
    (net (code "149") (name "unconnected-(LPC1-Pad31)") (class "Default")
      (node (ref "LPC1") (pin "31") (pinfunction "31_31") (pintype "passive"))
    )
    (net (code "150") (name "unconnected-(M1-FAULT-Pad2)") (class "Default")
      (node (ref "M1") (pin "2") (pinfunction "FAULT_2") (pintype "output"))
    )
    (net (code "151") (name "unconnected-(M2-FAULT-Pad2)") (class "Default")
      (node (ref "M2") (pin "2") (pinfunction "FAULT_2") (pintype "output"))
    )
    (net (code "152") (name "unconnected-(M3-FAULT-Pad2)") (class "Default")
      (node (ref "M3") (pin "2") (pinfunction "FAULT_2") (pintype "output"))
    )
    (net (code "153") (name "unconnected-(M4-FAULT-Pad2)") (class "Default")
      (node (ref "M4") (pin "2") (pinfunction "FAULT_2") (pintype "output"))
    )
    (net (code "154") (name "unconnected-(RJ1-PadNC)") (class "Default")
      (node (ref "RJ1") (pin "NC") (pinfunction "NC_NC") (pintype "bidirectional"))
    )
    (net (code "155") (name "unconnected-(U1-NC-Pad1)") (class "Default")
      (node (ref "U1") (pin "1") (pinfunction "NC_1") (pintype "bidirectional"))
    )
    (net (code "156") (name "unconnected-(U1-RSV-Pad8)") (class "Default")
      (node (ref "U1") (pin "8") (pinfunction "RSV_8") (pintype "bidirectional"))
    )
  )
)
